# e-ink-display-v003.net
KiCad netlist of a schematic drawn in EAGLE
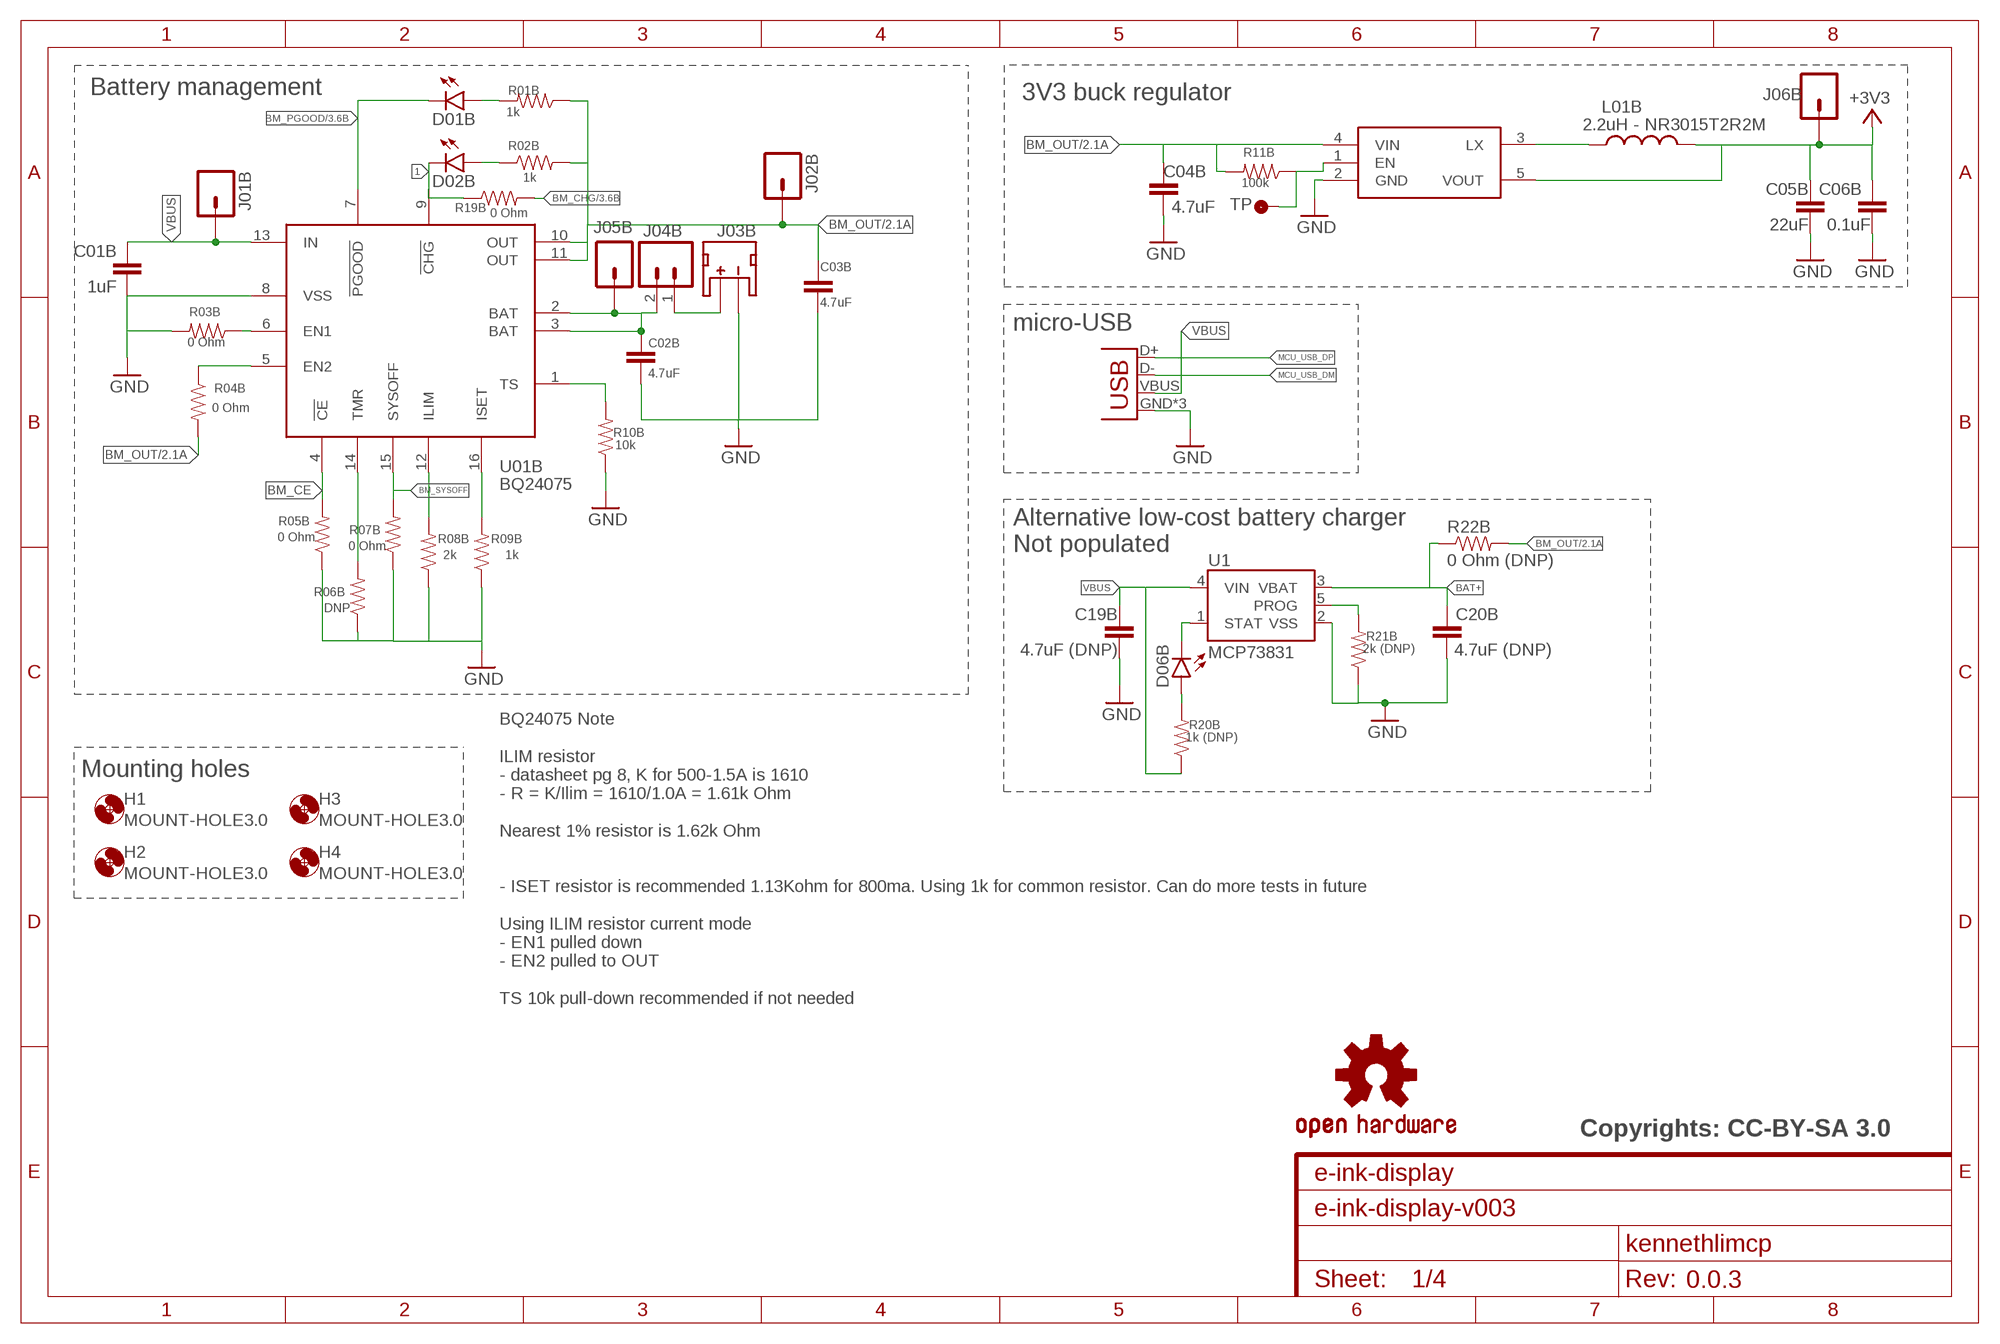
[diagram p0: schematic, sheet 1]
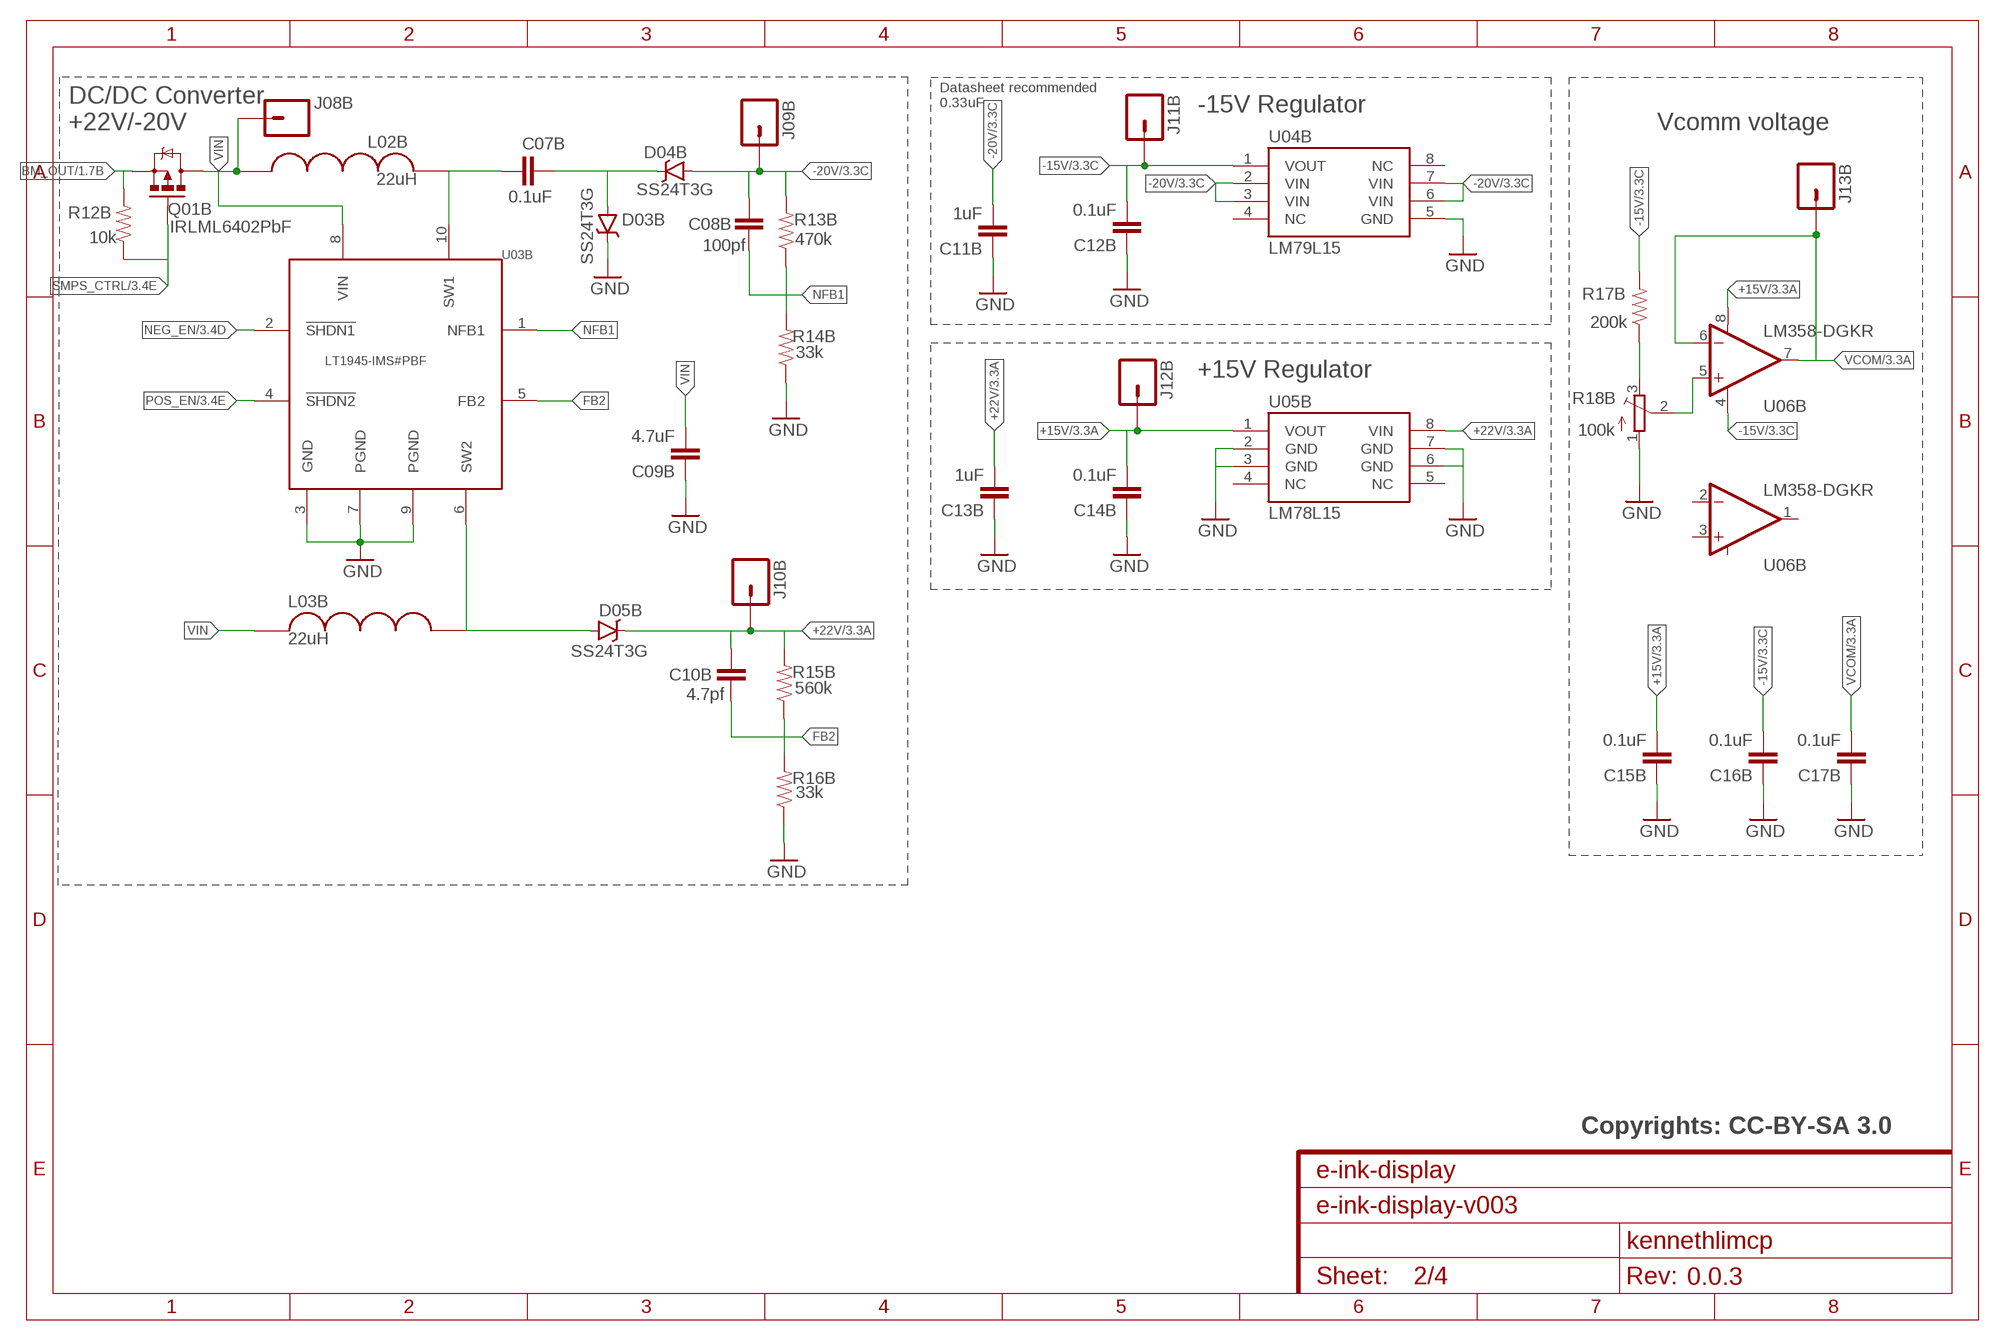
[diagram p1: schematic, sheet 2]
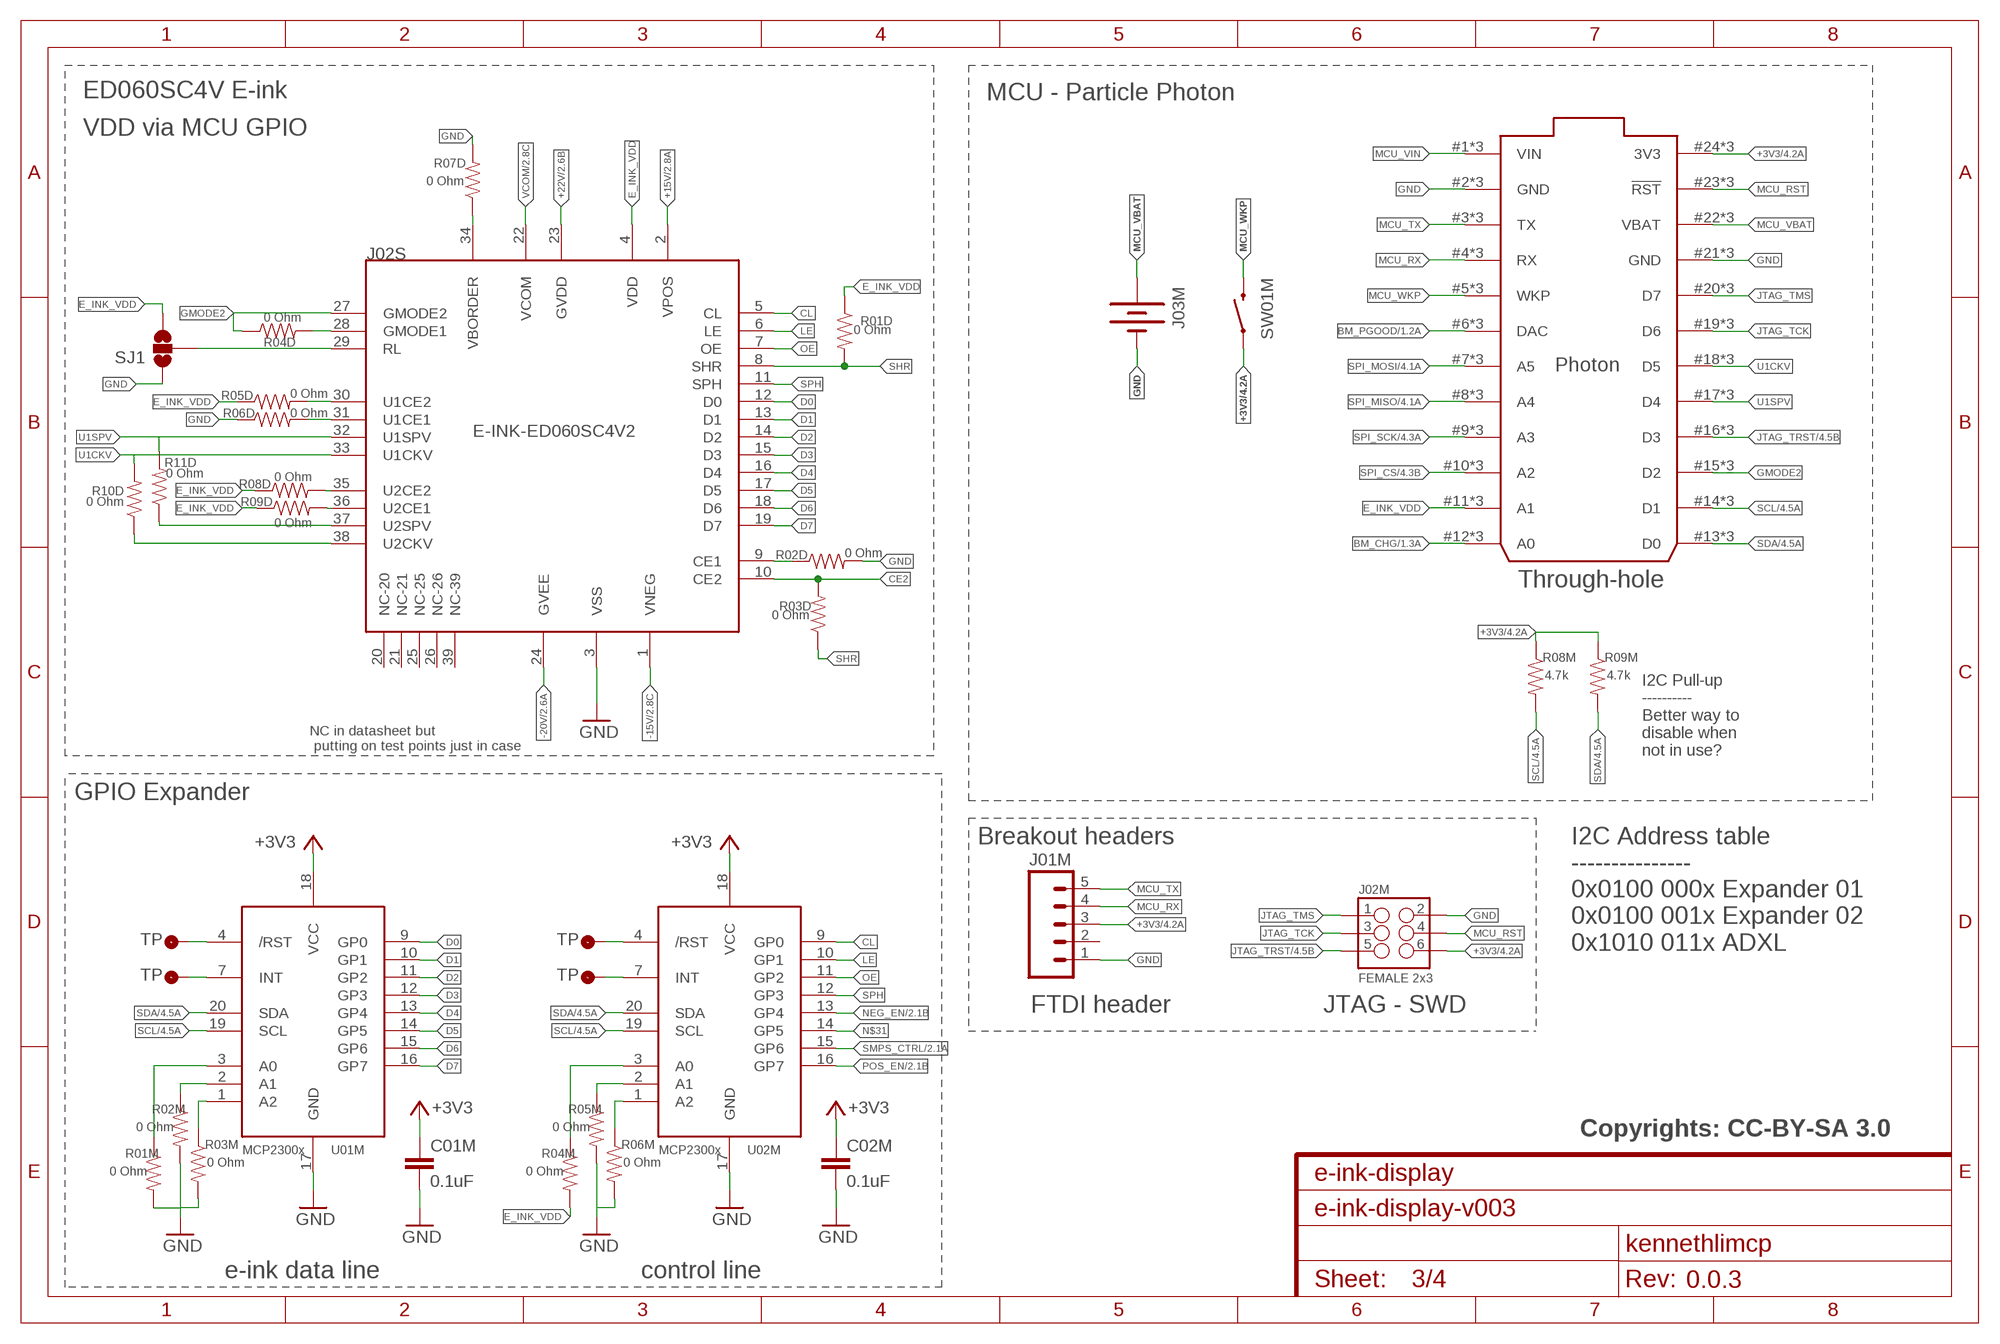
[diagram p2: schematic, sheet 3]
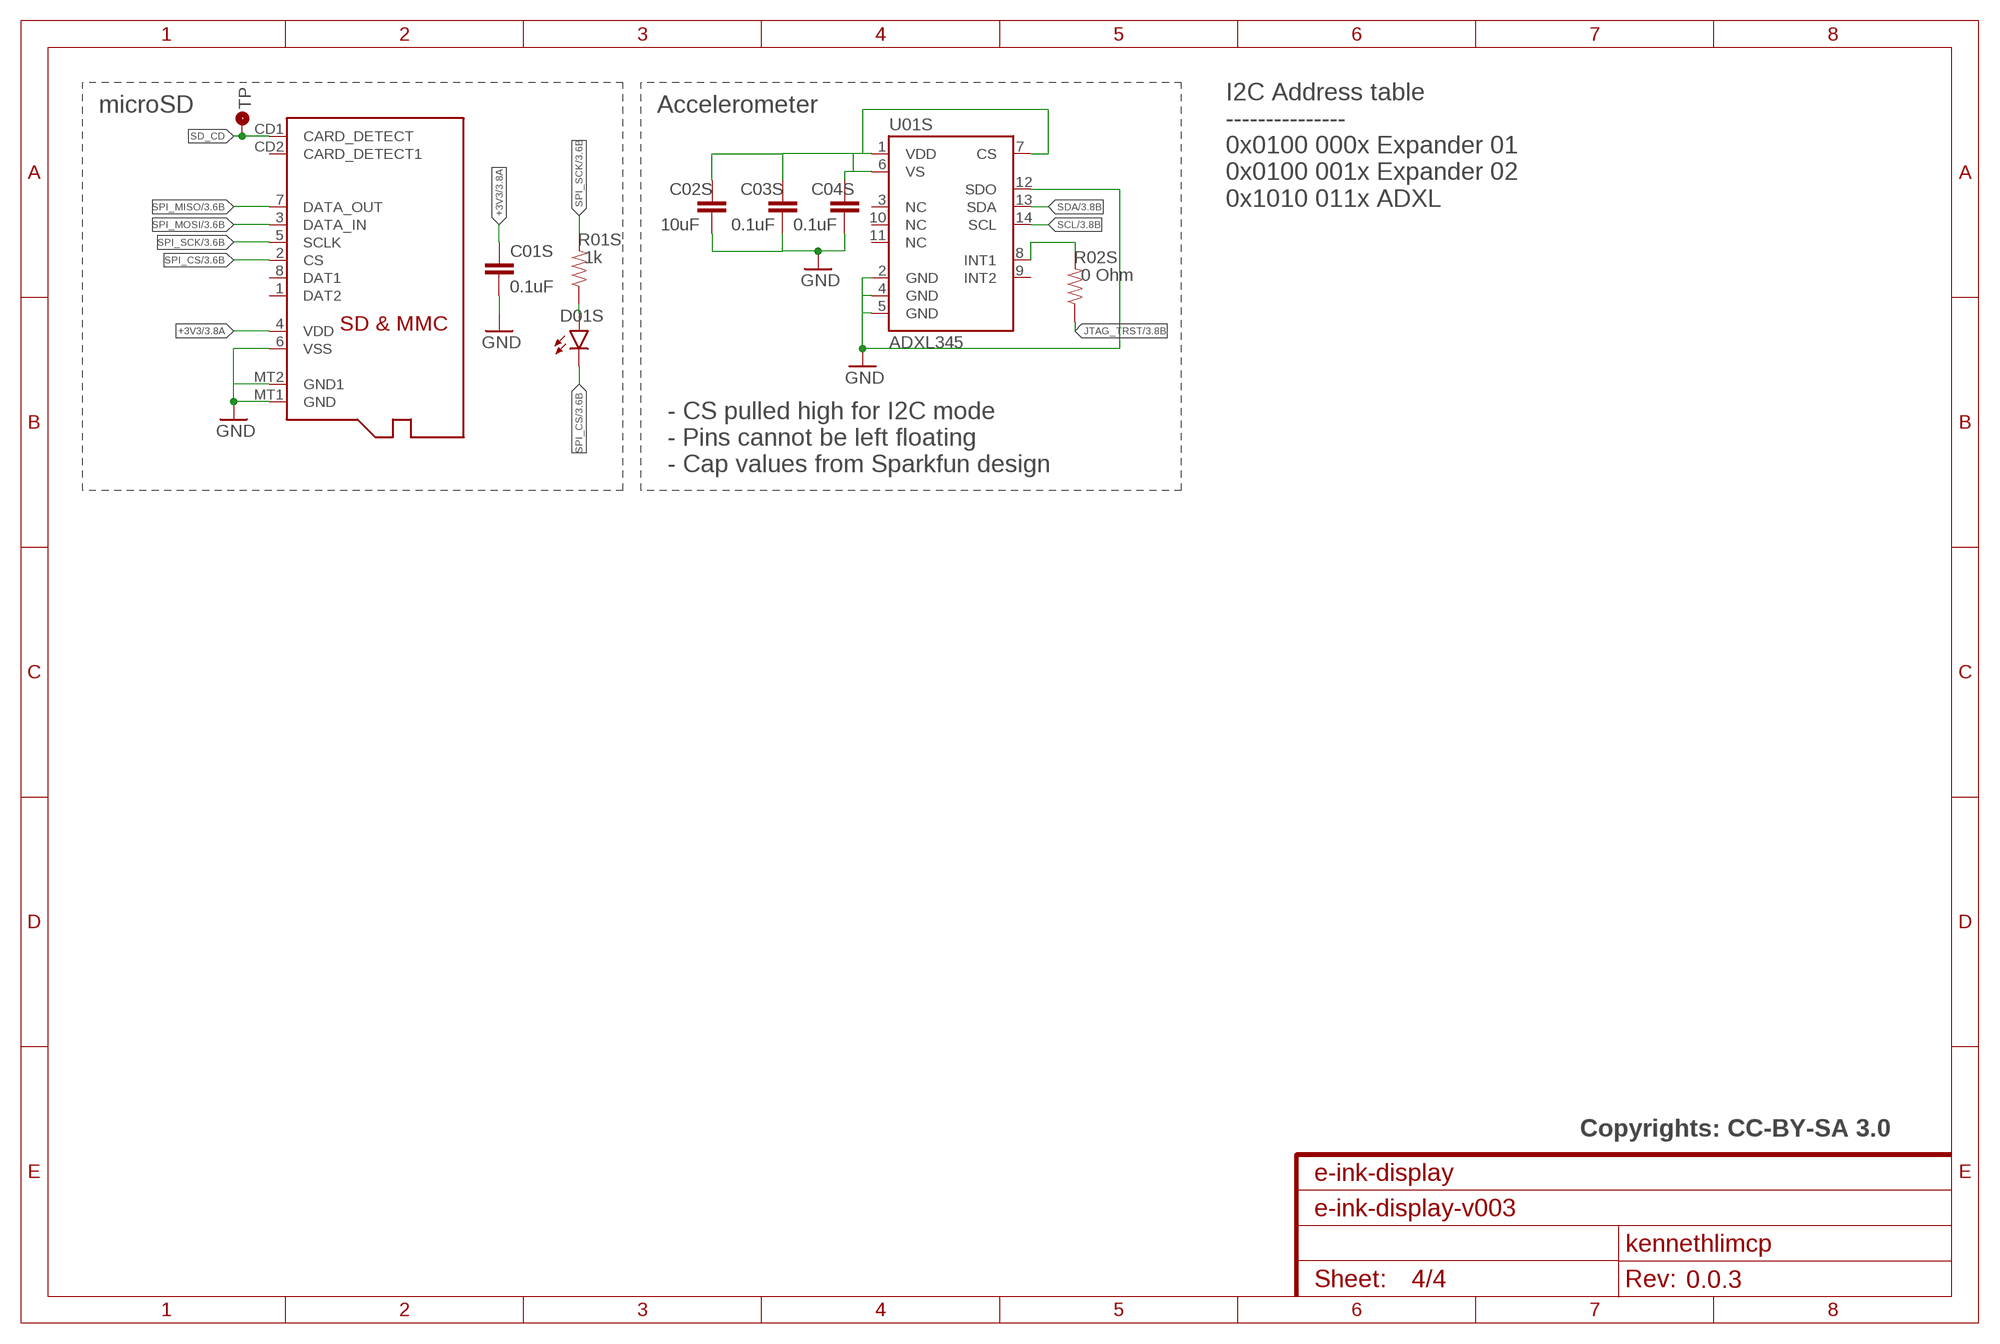
[diagram p3: schematic, sheet 4]

(export (version "E")
  (design (tool "Eeschema 10.0.6"))
  (components
    (comp (ref "C07B")
      (value "0.1uF")
      (footprint "eagle-import:0603-CAP")
      (libsource (lib "eagle-import") (part "CAP0603-CAP"))
    )
    (comp (ref "C08B")
      (value "100pf")
      (footprint "eagle-import:0603-CAP")
      (libsource (lib "eagle-import") (part "CAP0603-CAP"))
    )
    (comp (ref "C09B")
      (value "4.7uF")
      (footprint "eagle-import:0603-CAP")
      (libsource (lib "eagle-import") (part "CAP0603-CAP"))
    )
    (comp (ref "C10B")
      (value "4.7pf")
      (footprint "eagle-import:0603-CAP")
      (libsource (lib "eagle-import") (part "CAP0603-CAP"))
    )
    (comp (ref "C11B")
      (value "1uF")
      (footprint "eagle-import:0603-CAP")
      (libsource (lib "eagle-import") (part "CAP0603-CAP"))
    )
    (comp (ref "C12B")
      (value "0.1uF")
      (footprint "eagle-import:0603-CAP")
      (libsource (lib "eagle-import") (part "CAP0603-CAP"))
    )
    (comp (ref "C13B")
      (value "1uF")
      (footprint "eagle-import:0603-CAP")
      (libsource (lib "eagle-import") (part "CAP0603-CAP"))
    )
    (comp (ref "C14B")
      (value "0.1uF")
      (footprint "eagle-import:0603-CAP")
      (libsource (lib "eagle-import") (part "CAP0603-CAP"))
    )
    (comp (ref "C15B")
      (value "0.1uF")
      (footprint "eagle-import:0603-CAP")
      (libsource (lib "eagle-import") (part "CAP0603-CAP"))
    )
    (comp (ref "C16B")
      (value "0.1uF")
      (footprint "eagle-import:0603-CAP")
      (libsource (lib "eagle-import") (part "CAP0603-CAP"))
    )
    (comp (ref "C17B")
      (value "0.1uF")
      (footprint "eagle-import:0603-CAP")
      (libsource (lib "eagle-import") (part "CAP0603-CAP"))
    )
    (comp (ref "D03B")
      (value "SS24T3G")
      (footprint "eagle-import:SMA-DIODE")
      (libsource (lib "eagle-import") (part "SS24T3G"))
    )
    (comp (ref "D04B")
      (value "SS24T3G")
      (footprint "eagle-import:SMA-DIODE")
      (libsource (lib "eagle-import") (part "SS24T3G"))
    )
    (comp (ref "D05B")
      (value "SS24T3G")
      (footprint "eagle-import:SMA-DIODE")
      (libsource (lib "eagle-import") (part "SS24T3G"))
    )
    (comp (ref "J08B")
      (value "M01PTH")
      (footprint "eagle-import:1X01")
      (libsource (lib "eagle-import") (part "M01PTH"))
    )
    (comp (ref "J09B")
      (value "M01PTH")
      (footprint "eagle-import:1X01")
      (libsource (lib "eagle-import") (part "M01PTH"))
    )
    (comp (ref "J10B")
      (value "M01PTH")
      (footprint "eagle-import:1X01")
      (libsource (lib "eagle-import") (part "M01PTH"))
    )
    (comp (ref "J11B")
      (value "M01PTH")
      (footprint "eagle-import:1X01")
      (libsource (lib "eagle-import") (part "M01PTH"))
    )
    (comp (ref "J12B")
      (value "M01PTH")
      (footprint "eagle-import:1X01")
      (libsource (lib "eagle-import") (part "M01PTH"))
    )
    (comp (ref "J13B")
      (value "M01PTH")
      (footprint "eagle-import:1X01")
      (libsource (lib "eagle-import") (part "M01PTH"))
    )
    (comp (ref "L02B")
      (value "22uH")
      (footprint "eagle-import:4040(1515)")
      (libsource (lib "eagle-import") (part "INDUCTOR"))
    )
    (comp (ref "L03B")
      (value "22uH")
      (footprint "eagle-import:4040(1515)")
      (libsource (lib "eagle-import") (part "INDUCTOR"))
    )
    (comp (ref "Q01B")
      (value "IRLML6402PbF")
      (footprint "eagle-import:SOT23-3")
      (libsource (lib "eagle-import") (part "MOSFET-PCHANNELSMD"))
    )
    (comp (ref "R12B")
      (value "10k")
      (footprint "eagle-import:0603-RES")
      (libsource (lib "eagle-import") (part "RESISTOR0603"))
    )
    (comp (ref "R13B")
      (value "470k")
      (footprint "eagle-import:0603-RES")
      (libsource (lib "eagle-import") (part "RESISTOR0603"))
    )
    (comp (ref "R14B")
      (value "33k")
      (footprint "eagle-import:0603-RES")
      (libsource (lib "eagle-import") (part "RESISTOR0603"))
    )
    (comp (ref "R15B")
      (value "560k")
      (footprint "eagle-import:0603-RES")
      (libsource (lib "eagle-import") (part "RESISTOR0603"))
    )
    (comp (ref "R16B")
      (value "33k")
      (footprint "eagle-import:0603-RES")
      (libsource (lib "eagle-import") (part "RESISTOR0603"))
    )
    (comp (ref "R17B")
      (value "200k")
      (footprint "eagle-import:0603-RES")
      (libsource (lib "eagle-import") (part "RESISTOR0603"))
    )
    (comp (ref "R18B")
      (value "100k")
      (footprint "eagle-import:TC33X")
      (libsource (lib "eagle-import") (part "TRIMPOTTC33X"))
    )
    (comp (ref "U03B")
      (value "LT1945-IMS#PBF")
      (footprint "eagle-import:MSOP-10")
      (libsource (lib "eagle-import") (part "LT1945-IMS#PBF"))
    )
    (comp (ref "U04B")
      (value "LM79L15")
      (footprint "eagle-import:SO08")
      (libsource (lib "eagle-import") (part "LM79L15"))
    )
    (comp (ref "U05B")
      (value "LM78L15")
      (footprint "eagle-import:SO08")
      (libsource (lib "eagle-import") (part "LM78L15"))
    )
    (comp (ref "U06B")
      (value "LM358-DGKR")
      (footprint "eagle-import:MSOP-8")
      (libsource (lib "eagle-import") (part "LM358-DGKR"))
    )
    (comp (ref "C01S")
      (value "0.1uF")
      (footprint "eagle-import:0603-CAP")
      (libsource (lib "eagle-import") (part "CAP0603-CAP"))
    )
    (comp (ref "C02S")
      (value "10uF")
      (footprint "eagle-import:0603-CAP")
      (libsource (lib "eagle-import") (part "CAP0603-CAP"))
    )
    (comp (ref "C03S")
      (value "0.1uF")
      (footprint "eagle-import:0603-CAP")
      (libsource (lib "eagle-import") (part "CAP0603-CAP"))
    )
    (comp (ref "C04S")
      (value "0.1uF")
      (footprint "eagle-import:0603-CAP")
      (libsource (lib "eagle-import") (part "CAP0603-CAP"))
    )
    (comp (ref "D01S")
      (value "LED0603")
      (footprint "eagle-import:LED-0603")
      (libsource (lib "eagle-import") (part "LED0603"))
    )
    (comp (ref "J01S")
      (value "MICROSD")
      (footprint "eagle-import:MICROSD")
      (libsource (lib "eagle-import") (part "MICROSD"))
    )
    (comp (ref "R01S")
      (value "1k")
      (footprint "eagle-import:0603-RES")
      (libsource (lib "eagle-import") (part "SparkFun-Resistors_RESISTOR0603-RES"))
    )
    (comp (ref "R02S")
      (value "0 Ohm")
      (footprint "eagle-import:0603-RES")
      (libsource (lib "eagle-import") (part "RESISTOR0603"))
    )
    (comp (ref "U$5")
      (value "TP3")
      (footprint "eagle-import:TP60_BOT")
      (libsource (lib "eagle-import") (part "TP3"))
    )
    (comp (ref "U01S")
      (value "ADXL345")
      (footprint "eagle-import:LGA14")
      (libsource (lib "eagle-import") (part "ADXL345"))
    )
    (comp (ref "C01M")
      (value "0.1uF")
      (footprint "eagle-import:0603-CAP")
      (libsource (lib "eagle-import") (part "CAP0603-CAP"))
    )
    (comp (ref "C02M")
      (value "0.1uF")
      (footprint "eagle-import:0603-CAP")
      (libsource (lib "eagle-import") (part "CAP0603-CAP"))
    )
    (comp (ref "J01M")
      (value "M05PTH")
      (footprint "eagle-import:1X05")
      (libsource (lib "eagle-import") (part "M05PTH"))
    )
    (comp (ref "J02M")
      (value "FEMALE 2x3")
      (footprint "eagle-import:2X3")
      (libsource (lib "eagle-import") (part "M03X2FEMALE"))
    )
    (comp (ref "J02S")
      (value "E-INK-ED060SC4V2")
      (footprint "eagle-import:FPC-0.3-39")
      (libsource (lib "eagle-import") (part "E-INK-ED060SC4V2"))
    )
    (comp (ref "J03M")
      (value "BATTERY20PTH")
      (footprint "eagle-import:BATTCOM_20MM_PTH")
      (libsource (lib "eagle-import") (part "BATTERY20PTH"))
    )
    (comp (ref "R01D")
      (value "0 Ohm")
      (footprint "eagle-import:0603-RES")
      (libsource (lib "eagle-import") (part "RESISTOR0603-RES"))
    )
    (comp (ref "R01M")
      (value "0 Ohm")
      (footprint "eagle-import:0603-RES")
      (libsource (lib "eagle-import") (part "RESISTOR0603-RES"))
    )
    (comp (ref "R02D")
      (value "0 Ohm")
      (footprint "eagle-import:0603-RES")
      (libsource (lib "eagle-import") (part "RESISTOR0603-RES"))
    )
    (comp (ref "R02M")
      (value "0 Ohm")
      (footprint "eagle-import:0603-RES")
      (libsource (lib "eagle-import") (part "RESISTOR0603-RES"))
    )
    (comp (ref "R03D")
      (value "0 Ohm")
      (footprint "eagle-import:0603-RES")
      (libsource (lib "eagle-import") (part "RESISTOR0603-RES"))
    )
    (comp (ref "R03M")
      (value "0 Ohm")
      (footprint "eagle-import:0603-RES")
      (libsource (lib "eagle-import") (part "RESISTOR0603-RES"))
    )
    (comp (ref "R04D")
      (value "0 Ohm")
      (footprint "eagle-import:0603-RES")
      (libsource (lib "eagle-import") (part "RESISTOR0603-RES"))
    )
    (comp (ref "R04M")
      (value "0 Ohm")
      (footprint "eagle-import:0603-RES")
      (libsource (lib "eagle-import") (part "RESISTOR0603-RES"))
    )
    (comp (ref "R05D")
      (value "0 Ohm")
      (footprint "eagle-import:0603-RES")
      (libsource (lib "eagle-import") (part "RESISTOR0603-RES"))
    )
    (comp (ref "R05M")
      (value "0 Ohm")
      (footprint "eagle-import:0603-RES")
      (libsource (lib "eagle-import") (part "RESISTOR0603-RES"))
    )
    (comp (ref "R06D")
      (value "0 Ohm")
      (footprint "eagle-import:0603-RES")
      (libsource (lib "eagle-import") (part "RESISTOR0603-RES"))
    )
    (comp (ref "R06M")
      (value "0 Ohm")
      (footprint "eagle-import:0603-RES")
      (libsource (lib "eagle-import") (part "RESISTOR0603-RES"))
    )
    (comp (ref "R07D")
      (value "0 Ohm")
      (footprint "eagle-import:0603-RES")
      (libsource (lib "eagle-import") (part "RESISTOR0603-RES"))
    )
    (comp (ref "R08D")
      (value "0 Ohm")
      (footprint "eagle-import:0603-RES")
      (libsource (lib "eagle-import") (part "RESISTOR0603-RES"))
    )
    (comp (ref "R08M")
      (value "4.7k")
      (footprint "eagle-import:0603-RES")
      (libsource (lib "eagle-import") (part "RESISTOR0603-RES"))
    )
    (comp (ref "R09D")
      (value "0 Ohm")
      (footprint "eagle-import:0603-RES")
      (libsource (lib "eagle-import") (part "RESISTOR0603-RES"))
    )
    (comp (ref "R09M")
      (value "4.7k")
      (footprint "eagle-import:0603-RES")
      (libsource (lib "eagle-import") (part "RESISTOR0603-RES"))
    )
    (comp (ref "R10D")
      (value "0 Ohm")
      (footprint "eagle-import:0603-RES")
      (libsource (lib "eagle-import") (part "RESISTOR0603-RES"))
    )
    (comp (ref "R11D")
      (value "0 Ohm")
      (footprint "eagle-import:0603-RES")
      (libsource (lib "eagle-import") (part "RESISTOR0603-RES"))
    )
    (comp (ref "SJ1")
      (value "SOLDERJUMPER_2WAYT")
      (footprint "eagle-import:SJ_2")
      (libsource (lib "eagle-import") (part "SOLDERJUMPER_2WAYT"))
    )
    (comp (ref "SW01M")
      (value "SWITCH-MOMENTARY-2PTH")
      (footprint "eagle-import:TACTILE-PTH")
      (libsource (lib "eagle-import") (part "SWITCH-MOMENTARY-2PTH"))
    )
    (comp (ref "U$1")
      (value "TP1")
      (footprint "eagle-import:TP35_BOT")
      (libsource (lib "eagle-import") (part "TP1"))
    )
    (comp (ref "U$2")
      (value "TP1")
      (footprint "eagle-import:TP35_BOT")
      (libsource (lib "eagle-import") (part "TP1"))
    )
    (comp (ref "U$3")
      (value "TP1")
      (footprint "eagle-import:TP35_BOT")
      (libsource (lib "eagle-import") (part "TP1"))
    )
    (comp (ref "U$4")
      (value "TP1")
      (footprint "eagle-import:TP35_BOT")
      (libsource (lib "eagle-import") (part "TP1"))
    )
    (comp (ref "U01M")
      (value "MCP2300X/QFN")
      (footprint "eagle-import:QFN-20(4X4)")
      (libsource (lib "eagle-import") (part "MCP2300X/QFN"))
    )
    (comp (ref "U02M")
      (value "MCP2300X/QFN")
      (footprint "eagle-import:QFN-20(4X4)")
      (libsource (lib "eagle-import") (part "MCP2300X/QFN"))
    )
    (comp (ref "U03M")
      (value "PHOTON_WITH_STACKABLE_HEADERS")
      (footprint "eagle-import:PHOTON_STACKABLE")
      (libsource (lib "eagle-import") (part "PHOTON_WITH_STACKABLE_HEADERS"))
    )
    (comp (ref "C01B")
      (value "1uF")
      (footprint "eagle-import:0603-CAP")
      (libsource (lib "eagle-import") (part "CAP0603-CAP"))
    )
    (comp (ref "C02B")
      (value "4.7uF")
      (footprint "eagle-import:0603-CAP")
      (libsource (lib "eagle-import") (part "CAP0603-CAP"))
    )
    (comp (ref "C03B")
      (value "4.7uF")
      (footprint "eagle-import:0603-CAP")
      (libsource (lib "eagle-import") (part "CAP0603-CAP"))
    )
    (comp (ref "C04B")
      (value "4.7uF")
      (footprint "eagle-import:0603-CAP")
      (libsource (lib "eagle-import") (part "CAP0603-CAP"))
    )
    (comp (ref "C05B")
      (value "22uF")
      (footprint "eagle-import:0603-CAP")
      (libsource (lib "eagle-import") (part "CAP0603-CAP"))
    )
    (comp (ref "C06B")
      (value "0.1uF")
      (footprint "eagle-import:0603-CAP")
      (libsource (lib "eagle-import") (part "CAP0603-CAP"))
    )
    (comp (ref "C19B")
      (value "4.7uF (DNP)")
      (footprint "eagle-import:0603-CAP")
      (libsource (lib "eagle-import") (part "CAP0603-CAP"))
    )
    (comp (ref "C20B")
      (value "4.7uF (DNP)")
      (footprint "eagle-import:0603-CAP")
      (libsource (lib "eagle-import") (part "CAP0603-CAP"))
    )
    (comp (ref "D01B")
      (value "LED0603")
      (footprint "eagle-import:LED-0603")
      (libsource (lib "eagle-import") (part "LED0603"))
    )
    (comp (ref "D02B")
      (value "LED0603")
      (footprint "eagle-import:LED-0603")
      (libsource (lib "eagle-import") (part "LED0603"))
    )
    (comp (ref "D06B")
      (value "LED0603")
      (footprint "eagle-import:LED-0603")
      (libsource (lib "eagle-import") (part "LED0603"))
    )
    (comp (ref "H1")
      (value "MOUNT-HOLE3.0")
      (footprint "eagle-import:3,0")
      (libsource (lib "eagle-import") (part "MOUNT-HOLE3.0"))
    )
    (comp (ref "H2")
      (value "MOUNT-HOLE3.0")
      (footprint "eagle-import:3,0")
      (libsource (lib "eagle-import") (part "MOUNT-HOLE3.0"))
    )
    (comp (ref "H3")
      (value "MOUNT-HOLE3.0")
      (footprint "eagle-import:3,0")
      (libsource (lib "eagle-import") (part "MOUNT-HOLE3.0"))
    )
    (comp (ref "H4")
      (value "MOUNT-HOLE3.0")
      (footprint "eagle-import:3,0")
      (libsource (lib "eagle-import") (part "MOUNT-HOLE3.0"))
    )
    (comp (ref "J01B")
      (value "M01PTH")
      (footprint "eagle-import:1X01")
      (libsource (lib "eagle-import") (part "M01PTH"))
    )
    (comp (ref "J02B")
      (value "M01PTH")
      (footprint "eagle-import:1X01")
      (libsource (lib "eagle-import") (part "M01PTH"))
    )
    (comp (ref "J03B")
      (value "JST_2MM_MALE")
      (footprint "eagle-import:JST-2-SMD")
      (libsource (lib "eagle-import") (part "JST_2MM_MALE"))
    )
    (comp (ref "J04B")
      (value "M02PTH")
      (footprint "eagle-import:1X02")
      (libsource (lib "eagle-import") (part "M02PTH"))
    )
    (comp (ref "J05B")
      (value "M01PTH")
      (footprint "eagle-import:1X01")
      (libsource (lib "eagle-import") (part "M01PTH"))
    )
    (comp (ref "J06B")
      (value "M01PTH")
      (footprint "eagle-import:1X01")
      (libsource (lib "eagle-import") (part "M01PTH"))
    )
    (comp (ref "J07B")
      (value "USBUSB-MICROB-SLOT-HOLE")
      (footprint "eagle-import:USB-MICROB-SLOT-HOLE")
      (libsource (lib "eagle-import") (part "USBUSB-MICROB-SLOT-HOLE"))
    )
    (comp (ref "L01B")
      (value "2.2uH - NR3015T2R2M")
      (footprint "eagle-import:INDUCTOR-NR3015")
      (libsource (lib "eagle-import") (part "INDUCTOR-SPARKFUNNR3015T4R7M"))
    )
    (comp (ref "LOGO1")
      (value "OSHW-LOGOPAD")
      (footprint "eagle-import:OSHW-LOGO-M-PAD")
      (libsource (lib "eagle-import") (part "OSHW-LOGOPAD"))
    )
    (comp (ref "R01B")
      (value "1k")
      (footprint "eagle-import:0603-RES")
      (libsource (lib "eagle-import") (part "SparkFun-Resistors_RESISTOR0603-RES"))
    )
    (comp (ref "R02B")
      (value "1k")
      (footprint "eagle-import:0603-RES")
      (libsource (lib "eagle-import") (part "SparkFun-Resistors_RESISTOR0603-RES"))
    )
    (comp (ref "R03B")
      (value "0 Ohm")
      (footprint "eagle-import:0603-RES")
      (libsource (lib "eagle-import") (part "SparkFun-Resistors_RESISTOR0603-RES"))
    )
    (comp (ref "R04B")
      (value "0 Ohm")
      (footprint "eagle-import:0603-RES")
      (libsource (lib "eagle-import") (part "RESISTOR0603"))
    )
    (comp (ref "R05B")
      (value "0 Ohm")
      (footprint "eagle-import:0603-RES")
      (libsource (lib "eagle-import") (part "RESISTOR0603"))
    )
    (comp (ref "R06B")
      (value "DNP")
      (footprint "eagle-import:0603-RES")
      (libsource (lib "eagle-import") (part "RESISTOR0603"))
    )
    (comp (ref "R07B")
      (value "0 Ohm")
      (footprint "eagle-import:0603-RES")
      (libsource (lib "eagle-import") (part "RESISTOR0603"))
    )
    (comp (ref "R08B")
      (value "2k")
      (footprint "eagle-import:0603-RES")
      (libsource (lib "eagle-import") (part "RESISTOR0603"))
    )
    (comp (ref "R09B")
      (value "1k")
      (footprint "eagle-import:0603-RES")
      (libsource (lib "eagle-import") (part "SparkFun-Resistors_RESISTOR0603-RES"))
    )
    (comp (ref "R10B")
      (value "10k")
      (footprint "eagle-import:0603-RES")
      (libsource (lib "eagle-import") (part "RESISTOR0603"))
    )
    (comp (ref "R11B")
      (value "100k")
      (footprint "eagle-import:0603-RES")
      (libsource (lib "eagle-import") (part "RESISTOR0603"))
    )
    (comp (ref "R19B")
      (value "0 Ohm")
      (footprint "eagle-import:0603-RES")
      (libsource (lib "eagle-import") (part "RESISTOR0603"))
    )
    (comp (ref "R20B")
      (value "1k (DNP)")
      (footprint "eagle-import:0603-RES")
      (libsource (lib "eagle-import") (part "RESISTOR0603"))
    )
    (comp (ref "R21B")
      (value "2k (DNP)")
      (footprint "eagle-import:0603-RES")
      (libsource (lib "eagle-import") (part "RESISTOR0603"))
    )
    (comp (ref "R22B")
      (value "0 Ohm (DNP)")
      (footprint "eagle-import:1206")
      (libsource (lib "eagle-import") (part "SparkFun-Resistors_RESISTOR1206"))
    )
    (comp (ref "TP01B")
      (value "TP1")
      (footprint "eagle-import:TP35_BOT")
      (libsource (lib "eagle-import") (part "TP1"))
    )
    (comp (ref "U1")
      (value "MCP73831")
      (footprint "eagle-import:SOT23-5")
      (libsource (lib "eagle-import") (part "MCP73831"))
    )
    (comp (ref "U01B")
      (value "BQ24075")
      (footprint "eagle-import:QFN-16")
      (libsource (lib "eagle-import") (part "BQ24075"))
    )
    (comp (ref "U02B")
      (value "R8008-33")
      (footprint "eagle-import:SOT23-5")
      (libsource (lib "eagle-import") (part "R8008-33"))
    )
  )
  (nets
    (net (code "1") (name "+3V3") (class "Default")
      (node (ref "C01M") (pin "1") (pinfunction "1_1") (pintype "passive"))
      (node (ref "C01S") (pin "1") (pinfunction "1_1") (pintype "passive"))
      (node (ref "C02M") (pin "1") (pinfunction "1_1") (pintype "passive"))
      (node (ref "C05B") (pin "2") (pinfunction "2_2") (pintype "passive"))
      (node (ref "C06B") (pin "2") (pinfunction "2_2") (pintype "passive"))
      (node (ref "J01M") (pin "3") (pinfunction "3_3") (pintype "passive"))
      (node (ref "J01S") (pin "4") (pinfunction "VDD_4") (pintype "power_in"))
      (node (ref "J02M") (pin "6") (pinfunction "6_6") (pintype "bidirectional"))
      (node (ref "J06B") (pin "1") (pinfunction "1_1") (pintype "passive"))
      (node (ref "L01B") (pin "2") (pinfunction "2_2") (pintype "passive"))
      (node (ref "R08M") (pin "1") (pinfunction "1_1") (pintype "passive"))
      (node (ref "R09M") (pin "1") (pinfunction "1_1") (pintype "passive"))
      (node (ref "SW01M") (pin "1") (pinfunction "1_1") (pintype "passive"))
      (node (ref "U01M") (pin "18") (pinfunction "VCC_18") (pintype "power_in"))
      (node (ref "U02B") (pin "5") (pinfunction "VOUT_5") (pintype "bidirectional"))
      (node (ref "U02M") (pin "18") (pinfunction "VCC_18") (pintype "power_in"))
      (node (ref "U03M") (pin "#24") (pinfunction "3V3_#24") (pintype "power_in"))
      (node (ref "U03M") (pin "24") (pinfunction "3V3_24") (pintype "power_in"))
      (node (ref "U03M") (pin "@24") (pinfunction "3V3_@24") (pintype "power_in"))
    )
    (net (code "2") (name "+15V") (class "Default")
      (node (ref "C14B") (pin "2") (pinfunction "2_2") (pintype "passive"))
      (node (ref "C15B") (pin "2") (pinfunction "2_2") (pintype "passive"))
      (node (ref "J02S") (pin "2") (pinfunction "VPOS_2") (pintype "bidirectional"))
      (node (ref "J12B") (pin "1") (pinfunction "1_1") (pintype "passive"))
      (node (ref "U05B") (pin "1") (pinfunction "VOUT_1") (pintype "bidirectional"))
      (node (ref "U06B") (pin "8") (pinfunction "V+_8") (pintype "power_in"))
    )
    (net (code "3") (name "+22V") (class "Default")
      (node (ref "C10B") (pin "2") (pinfunction "2_2") (pintype "passive"))
      (node (ref "C13B") (pin "2") (pinfunction "2_2") (pintype "passive"))
      (node (ref "D05B") (pin "C") (pinfunction "C_C") (pintype "passive"))
      (node (ref "J02S") (pin "23") (pinfunction "GVDD_23") (pintype "bidirectional"))
      (node (ref "J10B") (pin "1") (pinfunction "1_1") (pintype "passive"))
      (node (ref "R15B") (pin "2") (pinfunction "2_2") (pintype "passive"))
      (node (ref "U05B") (pin "8") (pinfunction "VIN_8") (pintype "bidirectional"))
    )
    (net (code "4") (name "-15V") (class "Default")
      (node (ref "C12B") (pin "2") (pinfunction "2_2") (pintype "passive"))
      (node (ref "C16B") (pin "2") (pinfunction "2_2") (pintype "passive"))
      (node (ref "J02S") (pin "1") (pinfunction "VNEG_1") (pintype "bidirectional"))
      (node (ref "J11B") (pin "1") (pinfunction "1_1") (pintype "passive"))
      (node (ref "R17B") (pin "2") (pinfunction "2_2") (pintype "passive"))
      (node (ref "U04B") (pin "1") (pinfunction "VOUT_1") (pintype "bidirectional"))
      (node (ref "U06B") (pin "4") (pinfunction "V-_4") (pintype "power_in"))
    )
    (net (code "5") (name "-20V") (class "Default")
      (node (ref "C08B") (pin "2") (pinfunction "2_2") (pintype "passive"))
      (node (ref "C11B") (pin "2") (pinfunction "2_2") (pintype "passive"))
      (node (ref "D04B") (pin "A") (pinfunction "A_A") (pintype "passive"))
      (node (ref "J02S") (pin "24") (pinfunction "GVEE_24") (pintype "bidirectional"))
      (node (ref "J09B") (pin "1") (pinfunction "1_1") (pintype "passive"))
      (node (ref "R13B") (pin "2") (pinfunction "2_2") (pintype "passive"))
      (node (ref "U04B") (pin "2") (pinfunction "VIN_2") (pintype "bidirectional"))
      (node (ref "U04B") (pin "3") (pinfunction "VIN_3") (pintype "bidirectional"))
      (node (ref "U04B") (pin "6") (pinfunction "VIN_6") (pintype "bidirectional"))
      (node (ref "U04B") (pin "7") (pinfunction "VIN_7") (pintype "bidirectional"))
    )
    (net (code "6") (name "1") (class "Default")
      (node (ref "D02B") (pin "C") (pinfunction "C_C") (pintype "passive"))
      (node (ref "R19B") (pin "1") (pinfunction "1_1") (pintype "passive"))
      (node (ref "U01B") (pin "9") (pinfunction "~{CHG}_9") (pintype "bidirectional"))
    )
    (net (code "7") (name "BAT+") (class "Default")
      (node (ref "C20B") (pin "2") (pinfunction "2_2") (pintype "passive"))
      (node (ref "J03B") (pin "2") (pinfunction "+_2") (pintype "bidirectional"))
      (node (ref "J04B") (pin "1") (pinfunction "1_1") (pintype "passive"))
      (node (ref "R22B") (pin "1") (pinfunction "1_1") (pintype "passive"))
      (node (ref "U1") (pin "3") (pinfunction "VBAT_3") (pintype "power_in"))
    )
    (net (code "8") (name "BM_CE") (class "Default")
      (node (ref "R05B") (pin "2") (pinfunction "2_2") (pintype "passive"))
      (node (ref "U01B") (pin "4") (pinfunction "~{CE}_4") (pintype "bidirectional"))
    )
    (net (code "9") (name "BM_CHG") (class "Default")
      (node (ref "R19B") (pin "2") (pinfunction "2_2") (pintype "passive"))
      (node (ref "U03M") (pin "#12") (pinfunction "A0_#12") (pintype "bidirectional"))
      (node (ref "U03M") (pin "12") (pinfunction "A0_12") (pintype "bidirectional"))
      (node (ref "U03M") (pin "@12") (pinfunction "A0_@12") (pintype "bidirectional"))
    )
    (net (code "10") (name "BM_OUT") (class "Default")
      (node (ref "C03B") (pin "2") (pinfunction "2_2") (pintype "passive"))
      (node (ref "C04B") (pin "2") (pinfunction "2_2") (pintype "passive"))
      (node (ref "J02B") (pin "1") (pinfunction "1_1") (pintype "passive"))
      (node (ref "Q01B") (pin "2") (pinfunction "S_2") (pintype "passive"))
      (node (ref "R01B") (pin "1") (pinfunction "1_1") (pintype "passive"))
      (node (ref "R02B") (pin "2") (pinfunction "2_2") (pintype "passive"))
      (node (ref "R04B") (pin "2") (pinfunction "2_2") (pintype "passive"))
      (node (ref "R11B") (pin "2") (pinfunction "2_2") (pintype "passive"))
      (node (ref "R12B") (pin "2") (pinfunction "2_2") (pintype "passive"))
      (node (ref "R22B") (pin "2") (pinfunction "2_2") (pintype "passive"))
      (node (ref "U01B") (pin "10") (pinfunction "OUT_10") (pintype "bidirectional"))
      (node (ref "U01B") (pin "11") (pinfunction "OUT_11") (pintype "bidirectional"))
      (node (ref "U02B") (pin "4") (pinfunction "VIN_4") (pintype "bidirectional"))
    )
    (net (code "11") (name "BM_PGOOD") (class "Default")
      (node (ref "D01B") (pin "C") (pinfunction "C_C") (pintype "passive"))
      (node (ref "U01B") (pin "7") (pinfunction "~{PGOOD}_7") (pintype "bidirectional"))
      (node (ref "U03M") (pin "#6") (pinfunction "DAC_#6") (pintype "bidirectional"))
      (node (ref "U03M") (pin "6") (pinfunction "DAC_6") (pintype "bidirectional"))
      (node (ref "U03M") (pin "@6") (pinfunction "DAC_@6") (pintype "bidirectional"))
    )
    (net (code "12") (name "BM_SYSOFF") (class "Default")
      (node (ref "R07B") (pin "2") (pinfunction "2_2") (pintype "passive"))
      (node (ref "U01B") (pin "15") (pinfunction "SYSOFF_15") (pintype "bidirectional"))
    )
    (net (code "13") (name "CE2") (class "Default")
      (node (ref "J02S") (pin "10") (pinfunction "CE2_10") (pintype "bidirectional"))
      (node (ref "R03D") (pin "2") (pinfunction "2_2") (pintype "passive"))
    )
    (net (code "14") (name "CL") (class "Default")
      (node (ref "J02S") (pin "5") (pinfunction "CL_5") (pintype "bidirectional"))
      (node (ref "U02M") (pin "9") (pinfunction "GP0_9") (pintype "bidirectional"))
    )
    (net (code "15") (name "D0") (class "Default")
      (node (ref "J02S") (pin "12") (pinfunction "D0_12") (pintype "bidirectional"))
      (node (ref "U01M") (pin "9") (pinfunction "GP0_9") (pintype "bidirectional"))
    )
    (net (code "16") (name "D1") (class "Default")
      (node (ref "J02S") (pin "13") (pinfunction "D1_13") (pintype "bidirectional"))
      (node (ref "U01M") (pin "10") (pinfunction "GP1_10") (pintype "bidirectional"))
    )
    (net (code "17") (name "D2") (class "Default")
      (node (ref "J02S") (pin "14") (pinfunction "D2_14") (pintype "bidirectional"))
      (node (ref "U01M") (pin "11") (pinfunction "GP2_11") (pintype "bidirectional"))
    )
    (net (code "18") (name "D3") (class "Default")
      (node (ref "J02S") (pin "15") (pinfunction "D3_15") (pintype "bidirectional"))
      (node (ref "U01M") (pin "12") (pinfunction "GP3_12") (pintype "bidirectional"))
    )
    (net (code "19") (name "D4") (class "Default")
      (node (ref "J02S") (pin "16") (pinfunction "D4_16") (pintype "bidirectional"))
      (node (ref "U01M") (pin "13") (pinfunction "GP4_13") (pintype "bidirectional"))
    )
    (net (code "20") (name "D5") (class "Default")
      (node (ref "J02S") (pin "17") (pinfunction "D5_17") (pintype "bidirectional"))
      (node (ref "U01M") (pin "14") (pinfunction "GP5_14") (pintype "bidirectional"))
    )
    (net (code "21") (name "D6") (class "Default")
      (node (ref "J02S") (pin "18") (pinfunction "D6_18") (pintype "bidirectional"))
      (node (ref "U01M") (pin "15") (pinfunction "GP6_15") (pintype "bidirectional"))
    )
    (net (code "22") (name "D7") (class "Default")
      (node (ref "J02S") (pin "19") (pinfunction "D7_19") (pintype "bidirectional"))
      (node (ref "U01M") (pin "16") (pinfunction "GP7_16") (pintype "bidirectional"))
    )
    (net (code "23") (name "E_INK_VDD") (class "Default")
      (node (ref "J02S") (pin "4") (pinfunction "VDD_4") (pintype "bidirectional"))
      (node (ref "R01D") (pin "1") (pinfunction "1_1") (pintype "passive"))
      (node (ref "R04M") (pin "2") (pinfunction "2_2") (pintype "passive"))
      (node (ref "R05D") (pin "1") (pinfunction "1_1") (pintype "passive"))
      (node (ref "R08D") (pin "1") (pinfunction "1_1") (pintype "passive"))
      (node (ref "R09D") (pin "1") (pinfunction "1_1") (pintype "passive"))
      (node (ref "SJ1") (pin "3") (pinfunction "3_3") (pintype "passive"))
      (node (ref "U03M") (pin "#11") (pinfunction "A1_#11") (pintype "bidirectional"))
      (node (ref "U03M") (pin "11") (pinfunction "A1_11") (pintype "bidirectional"))
      (node (ref "U03M") (pin "@11") (pinfunction "A1_@11") (pintype "bidirectional"))
    )
    (net (code "24") (name "FB2") (class "Default")
      (node (ref "C10B") (pin "1") (pinfunction "1_1") (pintype "passive"))
      (node (ref "R15B") (pin "1") (pinfunction "1_1") (pintype "passive"))
      (node (ref "R16B") (pin "2") (pinfunction "2_2") (pintype "passive"))
      (node (ref "U03B") (pin "5") (pinfunction "FB2_5") (pintype "bidirectional"))
    )
    (net (code "25") (name "GMODE2") (class "Default")
      (node (ref "J02S") (pin "27") (pinfunction "GMODE2_27") (pintype "bidirectional"))
      (node (ref "R04D") (pin "1") (pinfunction "1_1") (pintype "passive"))
      (node (ref "U03M") (pin "#15") (pinfunction "D2_#15") (pintype "bidirectional"))
      (node (ref "U03M") (pin "15") (pinfunction "D2_15") (pintype "bidirectional"))
      (node (ref "U03M") (pin "@15") (pinfunction "D2_@15") (pintype "bidirectional"))
    )
    (net (code "26") (name "GND") (class "Default")
      (node (ref "C01B") (pin "1") (pinfunction "1_1") (pintype "passive"))
      (node (ref "C01M") (pin "2") (pinfunction "2_2") (pintype "passive"))
      (node (ref "C01S") (pin "2") (pinfunction "2_2") (pintype "passive"))
      (node (ref "C02B") (pin "1") (pinfunction "1_1") (pintype "passive"))
      (node (ref "C02M") (pin "2") (pinfunction "2_2") (pintype "passive"))
      (node (ref "C02S") (pin "2") (pinfunction "2_2") (pintype "passive"))
      (node (ref "C03B") (pin "1") (pinfunction "1_1") (pintype "passive"))
      (node (ref "C03S") (pin "2") (pinfunction "2_2") (pintype "passive"))
      (node (ref "C04B") (pin "1") (pinfunction "1_1") (pintype "passive"))
      (node (ref "C04S") (pin "2") (pinfunction "2_2") (pintype "passive"))
      (node (ref "C05B") (pin "1") (pinfunction "1_1") (pintype "passive"))
      (node (ref "C06B") (pin "1") (pinfunction "1_1") (pintype "passive"))
      (node (ref "C09B") (pin "1") (pinfunction "1_1") (pintype "passive"))
      (node (ref "C11B") (pin "1") (pinfunction "1_1") (pintype "passive"))
      (node (ref "C12B") (pin "1") (pinfunction "1_1") (pintype "passive"))
      (node (ref "C13B") (pin "1") (pinfunction "1_1") (pintype "passive"))
      (node (ref "C14B") (pin "1") (pinfunction "1_1") (pintype "passive"))
      (node (ref "C15B") (pin "1") (pinfunction "1_1") (pintype "passive"))
      (node (ref "C16B") (pin "1") (pinfunction "1_1") (pintype "passive"))
      (node (ref "C17B") (pin "1") (pinfunction "1_1") (pintype "passive"))
      (node (ref "C19B") (pin "1") (pinfunction "1_1") (pintype "passive"))
      (node (ref "C20B") (pin "1") (pinfunction "1_1") (pintype "passive"))
      (node (ref "D03B") (pin "C") (pinfunction "C_C") (pintype "passive"))
      (node (ref "J01M") (pin "1") (pinfunction "1_1") (pintype "passive"))
      (node (ref "J01S") (pin "6") (pinfunction "VSS_6") (pintype "power_in"))
      (node (ref "J01S") (pin "MT1") (pinfunction "GND_MT1") (pintype "power_in"))
      (node (ref "J01S") (pin "MT2") (pinfunction "GND1_MT2") (pintype "power_in"))
      (node (ref "J02M") (pin "2") (pinfunction "2_2") (pintype "bidirectional"))
      (node (ref "J02S") (pin "3") (pinfunction "VSS_3") (pintype "bidirectional"))
      (node (ref "J03B") (pin "1") (pinfunction "-_1") (pintype "bidirectional"))
      (node (ref "J03M") (pin "2") (pinfunction "-_2") (pintype "power_in"))
      (node (ref "J07B") (pin "GND") (pinfunction "GND_GND") (pintype "bidirectional"))
      (node (ref "J07B") (pin "MT1") (pinfunction "GND_MT1") (pintype "bidirectional"))
      (node (ref "J07B") (pin "MT2") (pinfunction "GND_MT2") (pintype "bidirectional"))
      (node (ref "R01M") (pin "2") (pinfunction "2_2") (pintype "passive"))
      (node (ref "R02D") (pin "2") (pinfunction "2_2") (pintype "passive"))
      (node (ref "R02M") (pin "2") (pinfunction "2_2") (pintype "passive"))
      (node (ref "R03B") (pin "2") (pinfunction "2_2") (pintype "passive"))
      (node (ref "R03M") (pin "2") (pinfunction "2_2") (pintype "passive"))
      (node (ref "R05B") (pin "1") (pinfunction "1_1") (pintype "passive"))
      (node (ref "R05M") (pin "2") (pinfunction "2_2") (pintype "passive"))
      (node (ref "R06B") (pin "1") (pinfunction "1_1") (pintype "passive"))
      (node (ref "R06D") (pin "1") (pinfunction "1_1") (pintype "passive"))
      (node (ref "R06M") (pin "2") (pinfunction "2_2") (pintype "passive"))
      (node (ref "R07B") (pin "1") (pinfunction "1_1") (pintype "passive"))
      (node (ref "R07D") (pin "2") (pinfunction "2_2") (pintype "passive"))
      (node (ref "R08B") (pin "1") (pinfunction "1_1") (pintype "passive"))
      (node (ref "R09B") (pin "1") (pinfunction "1_1") (pintype "passive"))
      (node (ref "R10B") (pin "1") (pinfunction "1_1") (pintype "passive"))
      (node (ref "R14B") (pin "1") (pinfunction "1_1") (pintype "passive"))
      (node (ref "R16B") (pin "1") (pinfunction "1_1") (pintype "passive"))
      (node (ref "R18B") (pin "1") (pinfunction "A_1") (pintype "passive"))
      (node (ref "R21B") (pin "1") (pinfunction "1_1") (pintype "passive"))
      (node (ref "SJ1") (pin "1") (pinfunction "1_1") (pintype "passive"))
      (node (ref "U01B") (pin "8") (pinfunction "VSS_8") (pintype "bidirectional"))
      (node (ref "U01M") (pin "17") (pinfunction "GND_17") (pintype "power_in"))
      (node (ref "U01S") (pin "12") (pinfunction "SDO_12") (pintype "bidirectional"))
      (node (ref "U01S") (pin "2") (pinfunction "GND_2") (pintype "bidirectional"))
      (node (ref "U01S") (pin "4") (pinfunction "GND_4") (pintype "bidirectional"))
      (node (ref "U01S") (pin "5") (pinfunction "GND_5") (pintype "bidirectional"))
      (node (ref "U02B") (pin "2") (pinfunction "GND_2") (pintype "bidirectional"))
      (node (ref "U02M") (pin "17") (pinfunction "GND_17") (pintype "power_in"))
      (node (ref "U03B") (pin "3") (pinfunction "GND_3") (pintype "bidirectional"))
      (node (ref "U03B") (pin "7") (pinfunction "PGND_7") (pintype "bidirectional"))
      (node (ref "U03B") (pin "9") (pinfunction "PGND_9") (pintype "bidirectional"))
      (node (ref "U03M") (pin "#2") (pinfunction "GND_#2") (pintype "power_in"))
      (node (ref "U03M") (pin "#21") (pinfunction "GND_#21") (pintype "power_in"))
      (node (ref "U03M") (pin "2") (pinfunction "GND_2") (pintype "power_in"))
      (node (ref "U03M") (pin "21") (pinfunction "GND_21") (pintype "power_in"))
      (node (ref "U03M") (pin "@2") (pinfunction "GND_@2") (pintype "power_in"))
      (node (ref "U03M") (pin "@21") (pinfunction "GND_@21") (pintype "power_in"))
      (node (ref "U04B") (pin "5") (pinfunction "GND_5") (pintype "bidirectional"))
      (node (ref "U05B") (pin "2") (pinfunction "GND_2") (pintype "bidirectional"))
      (node (ref "U05B") (pin "3") (pinfunction "GND_3") (pintype "bidirectional"))
      (node (ref "U05B") (pin "6") (pinfunction "GND_6") (pintype "bidirectional"))
      (node (ref "U05B") (pin "7") (pinfunction "GND_7") (pintype "bidirectional"))
      (node (ref "U1") (pin "2") (pinfunction "VSS_2") (pintype "power_in"))
    )
    (net (code "27") (name "JTAG_TCK") (class "Default")
      (node (ref "J02M") (pin "3") (pinfunction "3_3") (pintype "bidirectional"))
      (node (ref "U03M") (pin "#19") (pinfunction "D6_#19") (pintype "bidirectional"))
      (node (ref "U03M") (pin "19") (pinfunction "D6_19") (pintype "bidirectional"))
      (node (ref "U03M") (pin "@19") (pinfunction "D6_@19") (pintype "bidirectional"))
    )
    (net (code "28") (name "JTAG_TMS") (class "Default")
      (node (ref "J02M") (pin "1") (pinfunction "1_1") (pintype "bidirectional"))
      (node (ref "U03M") (pin "#20") (pinfunction "D7_#20") (pintype "bidirectional"))
      (node (ref "U03M") (pin "20") (pinfunction "D7_20") (pintype "bidirectional"))
      (node (ref "U03M") (pin "@20") (pinfunction "D7_@20") (pintype "bidirectional"))
    )
    (net (code "29") (name "JTAG_TRST") (class "Default")
      (node (ref "J02M") (pin "5") (pinfunction "5_5") (pintype "bidirectional"))
      (node (ref "R02S") (pin "1") (pinfunction "1_1") (pintype "passive"))
      (node (ref "U03M") (pin "#16") (pinfunction "D3_#16") (pintype "bidirectional"))
      (node (ref "U03M") (pin "16") (pinfunction "D3_16") (pintype "bidirectional"))
      (node (ref "U03M") (pin "@16") (pinfunction "D3_@16") (pintype "bidirectional"))
    )
    (net (code "30") (name "LE") (class "Default")
      (node (ref "J02S") (pin "6") (pinfunction "LE_6") (pintype "bidirectional"))
      (node (ref "U02M") (pin "10") (pinfunction "GP1_10") (pintype "bidirectional"))
    )
    (net (code "31") (name "MCU_RST") (class "Default")
      (node (ref "J02M") (pin "4") (pinfunction "4_4") (pintype "bidirectional"))
      (node (ref "U03M") (pin "#23") (pinfunction "~{RST}_#23") (pintype "bidirectional"))
      (node (ref "U03M") (pin "23") (pinfunction "~{RST}_23") (pintype "bidirectional"))
      (node (ref "U03M") (pin "@23") (pinfunction "~{RST}_@23") (pintype "bidirectional"))
    )
    (net (code "32") (name "MCU_RX") (class "Default")
      (node (ref "J01M") (pin "4") (pinfunction "4_4") (pintype "passive"))
      (node (ref "U03M") (pin "#4") (pinfunction "RX_#4") (pintype "bidirectional"))
      (node (ref "U03M") (pin "4") (pinfunction "RX_4") (pintype "bidirectional"))
      (node (ref "U03M") (pin "@4") (pinfunction "RX_@4") (pintype "bidirectional"))
    )
    (net (code "33") (name "MCU_TX") (class "Default")
      (node (ref "J01M") (pin "5") (pinfunction "5_5") (pintype "passive"))
      (node (ref "U03M") (pin "#3") (pinfunction "TX_#3") (pintype "bidirectional"))
      (node (ref "U03M") (pin "3") (pinfunction "TX_3") (pintype "bidirectional"))
      (node (ref "U03M") (pin "@3") (pinfunction "TX_@3") (pintype "bidirectional"))
    )
    (net (code "34") (name "MCU_USB_DM") (class "Default")
      (node (ref "J07B") (pin "D-") (pinfunction "D-_D-") (pintype "bidirectional"))
    )
    (net (code "35") (name "MCU_USB_DP") (class "Default")
      (node (ref "J07B") (pin "D+") (pinfunction "D+_D+") (pintype "bidirectional"))
    )
    (net (code "36") (name "MCU_VBAT") (class "Default")
      (node (ref "J03M") (pin "1") (pinfunction "+_1") (pintype "power_in"))
      (node (ref "U03M") (pin "#22") (pinfunction "VBAT_#22") (pintype "power_in"))
      (node (ref "U03M") (pin "22") (pinfunction "VBAT_22") (pintype "power_in"))
      (node (ref "U03M") (pin "@22") (pinfunction "VBAT_@22") (pintype "power_in"))
    )
    (net (code "37") (name "MCU_VIN") (class "Default")
      (node (ref "U03M") (pin "#1") (pinfunction "VIN_#1") (pintype "power_in"))
      (node (ref "U03M") (pin "1") (pinfunction "VIN_1") (pintype "power_in"))
      (node (ref "U03M") (pin "@1") (pinfunction "VIN_@1") (pintype "power_in"))
    )
    (net (code "38") (name "MCU_WKP") (class "Default")
      (node (ref "SW01M") (pin "3") (pinfunction "2_3") (pintype "passive"))
      (node (ref "U03M") (pin "#5") (pinfunction "WKP_#5") (pintype "bidirectional"))
      (node (ref "U03M") (pin "5") (pinfunction "WKP_5") (pintype "bidirectional"))
      (node (ref "U03M") (pin "@5") (pinfunction "WKP_@5") (pintype "bidirectional"))
    )
    (net (code "39") (name "N$31") (class "Default")
      (node (ref "U02M") (pin "14") (pinfunction "GP5_14") (pintype "bidirectional"))
    )
    (net (code "40") (name "NEG_EN") (class "Default")
      (node (ref "U02M") (pin "13") (pinfunction "GP4_13") (pintype "bidirectional"))
      (node (ref "U03B") (pin "2") (pinfunction "~{SHDN1}_2") (pintype "bidirectional"))
    )
    (net (code "41") (name "NFB1") (class "Default")
      (node (ref "C08B") (pin "1") (pinfunction "1_1") (pintype "passive"))
      (node (ref "R13B") (pin "1") (pinfunction "1_1") (pintype "passive"))
      (node (ref "R14B") (pin "2") (pinfunction "2_2") (pintype "passive"))
      (node (ref "U03B") (pin "1") (pinfunction "NFB1_1") (pintype "bidirectional"))
    )
    (net (code "42") (name "Net-(C02B-Pad2)") (class "Default")
      (node (ref "C02B") (pin "2") (pinfunction "2_2") (pintype "passive"))
      (node (ref "J04B") (pin "2") (pinfunction "2_2") (pintype "passive"))
      (node (ref "J05B") (pin "1") (pinfunction "1_1") (pintype "passive"))
      (node (ref "U01B") (pin "2") (pinfunction "BAT_2") (pintype "bidirectional"))
      (node (ref "U01B") (pin "3") (pinfunction "BAT_3") (pintype "bidirectional"))
    )
    (net (code "43") (name "Net-(C07B-Pad2)") (class "Default")
      (node (ref "C07B") (pin "2") (pinfunction "2_2") (pintype "passive"))
      (node (ref "D03B") (pin "A") (pinfunction "A_A") (pintype "passive"))
      (node (ref "D04B") (pin "C") (pinfunction "C_C") (pintype "passive"))
    )
    (net (code "44") (name "Net-(D01B-PadA)") (class "Default")
      (node (ref "D01B") (pin "A") (pinfunction "A_A") (pintype "passive"))
      (node (ref "R01B") (pin "2") (pinfunction "2_2") (pintype "passive"))
    )
    (net (code "45") (name "Net-(D01S-PadA)") (class "Default")
      (node (ref "D01S") (pin "A") (pinfunction "A_A") (pintype "passive"))
      (node (ref "R01S") (pin "1") (pinfunction "1_1") (pintype "passive"))
    )
    (net (code "46") (name "Net-(D02B-PadA)") (class "Default")
      (node (ref "D02B") (pin "A") (pinfunction "A_A") (pintype "passive"))
      (node (ref "R02B") (pin "1") (pinfunction "1_1") (pintype "passive"))
    )
    (net (code "47") (name "Net-(D06B-PadA)") (class "Default")
      (node (ref "D06B") (pin "A") (pinfunction "A_A") (pintype "passive"))
      (node (ref "R20B") (pin "2") (pinfunction "2_2") (pintype "passive"))
    )
    (net (code "48") (name "Net-(J02S-CE1)") (class "Default")
      (node (ref "J02S") (pin "9") (pinfunction "CE1_9") (pintype "bidirectional"))
      (node (ref "R02D") (pin "1") (pinfunction "1_1") (pintype "passive"))
    )
    (net (code "49") (name "Net-(J02S-GMODE1)") (class "Default")
      (node (ref "J02S") (pin "28") (pinfunction "GMODE1_28") (pintype "bidirectional"))
      (node (ref "R04D") (pin "2") (pinfunction "2_2") (pintype "passive"))
    )
    (net (code "50") (name "Net-(J02S-RL)") (class "Default")
      (node (ref "J02S") (pin "29") (pinfunction "RL_29") (pintype "bidirectional"))
      (node (ref "SJ1") (pin "2") (pinfunction "2_2") (pintype "passive"))
    )
    (net (code "51") (name "Net-(J02S-U1CE1)") (class "Default")
      (node (ref "J02S") (pin "31") (pinfunction "U1CE1_31") (pintype "bidirectional"))
      (node (ref "R06D") (pin "2") (pinfunction "2_2") (pintype "passive"))
    )
    (net (code "52") (name "Net-(J02S-U1CE2)") (class "Default")
      (node (ref "J02S") (pin "30") (pinfunction "U1CE2_30") (pintype "bidirectional"))
      (node (ref "R05D") (pin "2") (pinfunction "2_2") (pintype "passive"))
    )
    (net (code "53") (name "Net-(J02S-U2CE1)") (class "Default")
      (node (ref "J02S") (pin "36") (pinfunction "U2CE1_36") (pintype "bidirectional"))
      (node (ref "R09D") (pin "2") (pinfunction "2_2") (pintype "passive"))
    )
    (net (code "54") (name "Net-(J02S-U2CE2)") (class "Default")
      (node (ref "J02S") (pin "35") (pinfunction "U2CE2_35") (pintype "bidirectional"))
      (node (ref "R08D") (pin "2") (pinfunction "2_2") (pintype "passive"))
    )
    (net (code "55") (name "Net-(J02S-U2CKV)") (class "Default")
      (node (ref "J02S") (pin "38") (pinfunction "U2CKV_38") (pintype "bidirectional"))
      (node (ref "R10D") (pin "1") (pinfunction "1_1") (pintype "passive"))
    )
    (net (code "56") (name "Net-(J02S-U2SPV)") (class "Default")
      (node (ref "J02S") (pin "37") (pinfunction "U2SPV_37") (pintype "bidirectional"))
      (node (ref "R11D") (pin "1") (pinfunction "1_1") (pintype "passive"))
    )
    (net (code "57") (name "Net-(J02S-VBORDER)") (class "Default")
      (node (ref "J02S") (pin "34") (pinfunction "VBORDER_34") (pintype "bidirectional"))
      (node (ref "R07D") (pin "1") (pinfunction "1_1") (pintype "passive"))
    )
    (net (code "58") (name "Net-(R18B-E)") (class "Default")
      (node (ref "R17B") (pin "1") (pinfunction "1_1") (pintype "passive"))
      (node (ref "R18B") (pin "3") (pinfunction "E_3") (pintype "passive"))
    )
    (net (code "59") (name "Net-(R18B-S)") (class "Default")
      (node (ref "R18B") (pin "2") (pinfunction "S_2") (pintype "passive"))
      (node (ref "U06B") (pin "5") (pinfunction "+IN2_5") (pintype "input"))
    )
    (net (code "60") (name "Net-(TP01B-TP)") (class "Default")
      (node (ref "R11B") (pin "1") (pinfunction "1_1") (pintype "passive"))
      (node (ref "TP01B") (pin "P$1") (pinfunction "TP_P$1") (pintype "bidirectional"))
      (node (ref "U02B") (pin "1") (pinfunction "EN_1") (pintype "bidirectional"))
    )
    (net (code "61") (name "Net-(U$1-TP)") (class "Default")
      (node (ref "U$1") (pin "P$1") (pinfunction "TP_P$1") (pintype "bidirectional"))
      (node (ref "U01M") (pin "4") (pinfunction "/RST_4") (pintype "input"))
    )
    (net (code "62") (name "Net-(U$2-TP)") (class "Default")
      (node (ref "U$2") (pin "P$1") (pinfunction "TP_P$1") (pintype "bidirectional"))
      (node (ref "U01M") (pin "7") (pinfunction "INT_7") (pintype "output"))
    )
    (net (code "63") (name "Net-(U$3-TP)") (class "Default")
      (node (ref "U$3") (pin "P$1") (pinfunction "TP_P$1") (pintype "bidirectional"))
      (node (ref "U02M") (pin "4") (pinfunction "/RST_4") (pintype "input"))
    )
    (net (code "64") (name "Net-(U$4-TP)") (class "Default")
      (node (ref "U$4") (pin "P$1") (pinfunction "TP_P$1") (pintype "bidirectional"))
      (node (ref "U02M") (pin "7") (pinfunction "INT_7") (pintype "output"))
    )
    (net (code "65") (name "Net-(U1-PROG)") (class "Default")
      (node (ref "R21B") (pin "2") (pinfunction "2_2") (pintype "passive"))
      (node (ref "U1") (pin "5") (pinfunction "PROG_5") (pintype "input"))
    )
    (net (code "66") (name "Net-(U1-STAT)") (class "Default")
      (node (ref "D06B") (pin "C") (pinfunction "C_C") (pintype "passive"))
      (node (ref "U1") (pin "1") (pinfunction "STAT_1") (pintype "output"))
    )
    (net (code "67") (name "Net-(U01B-EN1)") (class "Default")
      (node (ref "R03B") (pin "1") (pinfunction "1_1") (pintype "passive"))
      (node (ref "U01B") (pin "6") (pinfunction "EN1_6") (pintype "bidirectional"))
    )
    (net (code "68") (name "Net-(U01B-EN2)") (class "Default")
      (node (ref "R04B") (pin "1") (pinfunction "1_1") (pintype "passive"))
      (node (ref "U01B") (pin "5") (pinfunction "EN2_5") (pintype "bidirectional"))
    )
    (net (code "69") (name "Net-(U01B-ILIM)") (class "Default")
      (node (ref "R08B") (pin "2") (pinfunction "2_2") (pintype "passive"))
      (node (ref "U01B") (pin "12") (pinfunction "ILIM_12") (pintype "bidirectional"))
    )
    (net (code "70") (name "Net-(U01B-ISET)") (class "Default")
      (node (ref "R09B") (pin "2") (pinfunction "2_2") (pintype "passive"))
      (node (ref "U01B") (pin "16") (pinfunction "ISET_16") (pintype "bidirectional"))
    )
    (net (code "71") (name "Net-(U01B-TMR)") (class "Default")
      (node (ref "R06B") (pin "2") (pinfunction "2_2") (pintype "passive"))
      (node (ref "U01B") (pin "14") (pinfunction "TMR_14") (pintype "bidirectional"))
    )
    (net (code "72") (name "Net-(U01B-TS)") (class "Default")
      (node (ref "R10B") (pin "2") (pinfunction "2_2") (pintype "passive"))
      (node (ref "U01B") (pin "1") (pinfunction "TS_1") (pintype "bidirectional"))
    )
    (net (code "73") (name "Net-(U01M-A0)") (class "Default")
      (node (ref "R01M") (pin "1") (pinfunction "1_1") (pintype "passive"))
      (node (ref "U01M") (pin "3") (pinfunction "A0_3") (pintype "input"))
    )
    (net (code "74") (name "Net-(U01M-A1)") (class "Default")
      (node (ref "R02M") (pin "1") (pinfunction "1_1") (pintype "passive"))
      (node (ref "U01M") (pin "2") (pinfunction "A1_2") (pintype "input"))
    )
    (net (code "75") (name "Net-(U01M-A2)") (class "Default")
      (node (ref "R03M") (pin "1") (pinfunction "1_1") (pintype "passive"))
      (node (ref "U01M") (pin "1") (pinfunction "A2_1") (pintype "input"))
    )
    (net (code "76") (name "Net-(U01S-CS)") (class "Default")
      (node (ref "C02S") (pin "1") (pinfunction "1_1") (pintype "passive"))
      (node (ref "C03S") (pin "1") (pinfunction "1_1") (pintype "passive"))
      (node (ref "C04S") (pin "1") (pinfunction "1_1") (pintype "passive"))
      (node (ref "U01S") (pin "1") (pinfunction "VDD_1") (pintype "bidirectional"))
      (node (ref "U01S") (pin "6") (pinfunction "VS_6") (pintype "bidirectional"))
      (node (ref "U01S") (pin "7") (pinfunction "CS_7") (pintype "bidirectional"))
    )
    (net (code "77") (name "Net-(U01S-INT1)") (class "Default")
      (node (ref "R02S") (pin "2") (pinfunction "2_2") (pintype "passive"))
      (node (ref "U01S") (pin "8") (pinfunction "INT1_8") (pintype "bidirectional"))
    )
    (net (code "78") (name "Net-(U02B-LX)") (class "Default")
      (node (ref "L01B") (pin "1") (pinfunction "1_1") (pintype "passive"))
      (node (ref "U02B") (pin "3") (pinfunction "LX_3") (pintype "bidirectional"))
    )
    (net (code "79") (name "Net-(U02M-A0)") (class "Default")
      (node (ref "R04M") (pin "1") (pinfunction "1_1") (pintype "passive"))
      (node (ref "U02M") (pin "3") (pinfunction "A0_3") (pintype "input"))
    )
    (net (code "80") (name "Net-(U02M-A1)") (class "Default")
      (node (ref "R05M") (pin "1") (pinfunction "1_1") (pintype "passive"))
      (node (ref "U02M") (pin "2") (pinfunction "A1_2") (pintype "input"))
    )
    (net (code "81") (name "Net-(U02M-A2)") (class "Default")
      (node (ref "R06M") (pin "1") (pinfunction "1_1") (pintype "passive"))
      (node (ref "U02M") (pin "1") (pinfunction "A2_1") (pintype "input"))
    )
    (net (code "82") (name "Net-(U03B-SW1)") (class "Default")
      (node (ref "C07B") (pin "1") (pinfunction "1_1") (pintype "passive"))
      (node (ref "L02B") (pin "P$2") (pinfunction "P$2_P$2") (pintype "bidirectional"))
      (node (ref "U03B") (pin "10") (pinfunction "SW1_10") (pintype "bidirectional"))
    )
    (net (code "83") (name "Net-(U03B-SW2)") (class "Default")
      (node (ref "D05B") (pin "A") (pinfunction "A_A") (pintype "passive"))
      (node (ref "L03B") (pin "P$2") (pinfunction "P$2_P$2") (pintype "bidirectional"))
      (node (ref "U03B") (pin "6") (pinfunction "SW2_6") (pintype "bidirectional"))
    )
    (net (code "84") (name "OE") (class "Default")
      (node (ref "J02S") (pin "7") (pinfunction "OE_7") (pintype "bidirectional"))
      (node (ref "U02M") (pin "11") (pinfunction "GP2_11") (pintype "bidirectional"))
    )
    (net (code "85") (name "POS_EN") (class "Default")
      (node (ref "U02M") (pin "16") (pinfunction "GP7_16") (pintype "bidirectional"))
      (node (ref "U03B") (pin "4") (pinfunction "~{SHDN2}_4") (pintype "bidirectional"))
    )
    (net (code "86") (name "SCL") (class "Default")
      (node (ref "R08M") (pin "2") (pinfunction "2_2") (pintype "passive"))
      (node (ref "U01M") (pin "19") (pinfunction "SCL_19") (pintype "bidirectional"))
      (node (ref "U01S") (pin "14") (pinfunction "SCL_14") (pintype "bidirectional"))
      (node (ref "U02M") (pin "19") (pinfunction "SCL_19") (pintype "bidirectional"))
      (node (ref "U03M") (pin "#14") (pinfunction "D1_#14") (pintype "bidirectional"))
      (node (ref "U03M") (pin "14") (pinfunction "D1_14") (pintype "bidirectional"))
      (node (ref "U03M") (pin "@14") (pinfunction "D1_@14") (pintype "bidirectional"))
    )
    (net (code "87") (name "SDA") (class "Default")
      (node (ref "R09M") (pin "2") (pinfunction "2_2") (pintype "passive"))
      (node (ref "U01M") (pin "20") (pinfunction "SDA_20") (pintype "bidirectional"))
      (node (ref "U01S") (pin "13") (pinfunction "SDA_13") (pintype "bidirectional"))
      (node (ref "U02M") (pin "20") (pinfunction "SDA_20") (pintype "bidirectional"))
      (node (ref "U03M") (pin "#13") (pinfunction "D0_#13") (pintype "bidirectional"))
      (node (ref "U03M") (pin "13") (pinfunction "D0_13") (pintype "bidirectional"))
      (node (ref "U03M") (pin "@13") (pinfunction "D0_@13") (pintype "bidirectional"))
    )
    (net (code "88") (name "SD_CD") (class "Default")
      (node (ref "J01S") (pin "CD1") (pinfunction "CARD_DETECT_CD1") (pintype "passive"))
      (node (ref "U$5") (pin "P$1") (pinfunction "TP_P$1") (pintype "bidirectional"))
    )
    (net (code "89") (name "SHR") (class "Default")
      (node (ref "J02S") (pin "8") (pinfunction "SHR_8") (pintype "bidirectional"))
      (node (ref "R01D") (pin "2") (pinfunction "2_2") (pintype "passive"))
      (node (ref "R03D") (pin "1") (pinfunction "1_1") (pintype "passive"))
    )
    (net (code "90") (name "SMPS_CTRL") (class "Default")
      (node (ref "Q01B") (pin "1") (pinfunction "G_1") (pintype "passive"))
      (node (ref "R12B") (pin "1") (pinfunction "1_1") (pintype "passive"))
      (node (ref "U02M") (pin "15") (pinfunction "GP6_15") (pintype "bidirectional"))
    )
    (net (code "91") (name "SPH") (class "Default")
      (node (ref "J02S") (pin "11") (pinfunction "SPH_11") (pintype "bidirectional"))
      (node (ref "U02M") (pin "12") (pinfunction "GP3_12") (pintype "bidirectional"))
    )
    (net (code "92") (name "SPI_CS") (class "Default")
      (node (ref "D01S") (pin "C") (pinfunction "C_C") (pintype "passive"))
      (node (ref "J01S") (pin "2") (pinfunction "CS_2") (pintype "input"))
      (node (ref "U03M") (pin "#10") (pinfunction "A2_#10") (pintype "bidirectional"))
      (node (ref "U03M") (pin "10") (pinfunction "A2_10") (pintype "bidirectional"))
      (node (ref "U03M") (pin "@10") (pinfunction "A2_@10") (pintype "bidirectional"))
    )
    (net (code "93") (name "SPI_MISO") (class "Default")
      (node (ref "J01S") (pin "7") (pinfunction "DATA_OUT_7") (pintype "output"))
      (node (ref "U03M") (pin "#8") (pinfunction "A4_#8") (pintype "bidirectional"))
      (node (ref "U03M") (pin "8") (pinfunction "A4_8") (pintype "bidirectional"))
      (node (ref "U03M") (pin "@8") (pinfunction "A4_@8") (pintype "bidirectional"))
    )
    (net (code "94") (name "SPI_MOSI") (class "Default")
      (node (ref "J01S") (pin "3") (pinfunction "DATA_IN_3") (pintype "input"))
      (node (ref "U03M") (pin "#7") (pinfunction "A5_#7") (pintype "bidirectional"))
      (node (ref "U03M") (pin "7") (pinfunction "A5_7") (pintype "bidirectional"))
      (node (ref "U03M") (pin "@7") (pinfunction "A5_@7") (pintype "bidirectional"))
    )
    (net (code "95") (name "SPI_SCK") (class "Default")
      (node (ref "J01S") (pin "5") (pinfunction "SCLK_5") (pintype "input"))
      (node (ref "R01S") (pin "2") (pinfunction "2_2") (pintype "passive"))
      (node (ref "U03M") (pin "#9") (pinfunction "A3_#9") (pintype "bidirectional"))
      (node (ref "U03M") (pin "9") (pinfunction "A3_9") (pintype "bidirectional"))
      (node (ref "U03M") (pin "@9") (pinfunction "A3_@9") (pintype "bidirectional"))
    )
    (net (code "96") (name "U1CKV") (class "Default")
      (node (ref "J02S") (pin "33") (pinfunction "U1CKV_33") (pintype "bidirectional"))
      (node (ref "R10D") (pin "2") (pinfunction "2_2") (pintype "passive"))
      (node (ref "U03M") (pin "#18") (pinfunction "D5_#18") (pintype "bidirectional"))
      (node (ref "U03M") (pin "18") (pinfunction "D5_18") (pintype "bidirectional"))
      (node (ref "U03M") (pin "@18") (pinfunction "D5_@18") (pintype "bidirectional"))
    )
    (net (code "97") (name "U1SPV") (class "Default")
      (node (ref "J02S") (pin "32") (pinfunction "U1SPV_32") (pintype "bidirectional"))
      (node (ref "R11D") (pin "2") (pinfunction "2_2") (pintype "passive"))
      (node (ref "U03M") (pin "#17") (pinfunction "D4_#17") (pintype "bidirectional"))
      (node (ref "U03M") (pin "17") (pinfunction "D4_17") (pintype "bidirectional"))
      (node (ref "U03M") (pin "@17") (pinfunction "D4_@17") (pintype "bidirectional"))
    )
    (net (code "98") (name "VBUS") (class "Default")
      (node (ref "C01B") (pin "2") (pinfunction "2_2") (pintype "passive"))
      (node (ref "C19B") (pin "2") (pinfunction "2_2") (pintype "passive"))
      (node (ref "J01B") (pin "1") (pinfunction "1_1") (pintype "passive"))
      (node (ref "J07B") (pin "VBUS") (pinfunction "VBUS_VBUS") (pintype "bidirectional"))
      (node (ref "R20B") (pin "1") (pinfunction "1_1") (pintype "passive"))
      (node (ref "U01B") (pin "13") (pinfunction "IN_13") (pintype "bidirectional"))
      (node (ref "U1") (pin "4") (pinfunction "VIN_4") (pintype "power_in"))
    )
    (net (code "99") (name "VCOM") (class "Default")
      (node (ref "C17B") (pin "2") (pinfunction "2_2") (pintype "passive"))
      (node (ref "J02S") (pin "22") (pinfunction "VCOM_22") (pintype "bidirectional"))
      (node (ref "J13B") (pin "1") (pinfunction "1_1") (pintype "passive"))
      (node (ref "U06B") (pin "6") (pinfunction "-IN2_6") (pintype "input"))
      (node (ref "U06B") (pin "7") (pinfunction "OUT2_7") (pintype "output"))
    )
    (net (code "100") (name "VIN") (class "Default")
      (node (ref "C09B") (pin "2") (pinfunction "2_2") (pintype "passive"))
      (node (ref "J08B") (pin "1") (pinfunction "1_1") (pintype "passive"))
      (node (ref "L02B") (pin "P$1") (pinfunction "P$1_P$1") (pintype "bidirectional"))
      (node (ref "L03B") (pin "P$1") (pinfunction "P$1_P$1") (pintype "bidirectional"))
      (node (ref "Q01B") (pin "3") (pinfunction "D_3") (pintype "passive"))
      (node (ref "U03B") (pin "8") (pinfunction "VIN_8") (pintype "bidirectional"))
    )
    (net (code "101") (name "unconnected-(J01M-Pad2)") (class "Default")
      (node (ref "J01M") (pin "2") (pinfunction "2_2") (pintype "passive"))
    )
    (net (code "102") (name "unconnected-(J01S-CARD_DETECT1-PadCD2)") (class "Default")
      (node (ref "J01S") (pin "CD2") (pinfunction "CARD_DETECT1_CD2") (pintype "passive"))
    )
    (net (code "103") (name "unconnected-(J01S-DAT1-Pad8)") (class "Default")
      (node (ref "J01S") (pin "8") (pinfunction "DAT1_8") (pintype "bidirectional"))
    )
    (net (code "104") (name "unconnected-(J01S-DAT2-Pad1)") (class "Default")
      (node (ref "J01S") (pin "1") (pinfunction "DAT2_1") (pintype "bidirectional"))
    )
    (net (code "105") (name "unconnected-(J02S-NC-20-Pad20)") (class "Default")
      (node (ref "J02S") (pin "20") (pinfunction "NC-20_20") (pintype "bidirectional"))
    )
    (net (code "106") (name "unconnected-(J02S-NC-21-Pad21)") (class "Default")
      (node (ref "J02S") (pin "21") (pinfunction "NC-21_21") (pintype "bidirectional"))
    )
    (net (code "107") (name "unconnected-(J02S-NC-25-Pad25)") (class "Default")
      (node (ref "J02S") (pin "25") (pinfunction "NC-25_25") (pintype "bidirectional"))
    )
    (net (code "108") (name "unconnected-(J02S-NC-26-Pad26)") (class "Default")
      (node (ref "J02S") (pin "26") (pinfunction "NC-26_26") (pintype "bidirectional"))
    )
    (net (code "109") (name "unconnected-(J02S-NC-39-Pad39)") (class "Default")
      (node (ref "J02S") (pin "39") (pinfunction "NC-39_39") (pintype "bidirectional"))
    )
    (net (code "110") (name "unconnected-(J03B-PAD1-PadNC1)") (class "Default")
      (node (ref "J03B") (pin "NC1") (pinfunction "PAD1_NC1") (pintype "bidirectional"))
    )
    (net (code "111") (name "unconnected-(J03B-PAD2-PadNC2)") (class "Default")
      (node (ref "J03B") (pin "NC2") (pinfunction "PAD2_NC2") (pintype "bidirectional"))
    )
    (net (code "112") (name "unconnected-(U01S-INT2-Pad9)") (class "Default")
      (node (ref "U01S") (pin "9") (pinfunction "INT2_9") (pintype "bidirectional"))
    )
    (net (code "113") (name "unconnected-(U01S-NC-Pad3)") (class "Default")
      (node (ref "U01S") (pin "3") (pinfunction "NC_3") (pintype "bidirectional"))
    )
    (net (code "114") (name "unconnected-(U01S-NC-Pad10)") (class "Default")
      (node (ref "U01S") (pin "10") (pinfunction "NC_10") (pintype "bidirectional"))
    )
    (net (code "115") (name "unconnected-(U01S-NC-Pad11)") (class "Default")
      (node (ref "U01S") (pin "11") (pinfunction "NC_11") (pintype "bidirectional"))
    )
    (net (code "116") (name "unconnected-(U04B-NC-Pad4)") (class "Default")
      (node (ref "U04B") (pin "4") (pinfunction "NC_4") (pintype "bidirectional"))
    )
    (net (code "117") (name "unconnected-(U04B-NC-Pad8)") (class "Default")
      (node (ref "U04B") (pin "8") (pinfunction "NC_8") (pintype "bidirectional"))
    )
    (net (code "118") (name "unconnected-(U05B-NC-Pad4)") (class "Default")
      (node (ref "U05B") (pin "4") (pinfunction "NC_4") (pintype "bidirectional"))
    )
    (net (code "119") (name "unconnected-(U05B-NC-Pad5)") (class "Default")
      (node (ref "U05B") (pin "5") (pinfunction "NC_5") (pintype "bidirectional"))
    )
    (net (code "120") (name "unconnected-(U06B-+IN1-Pad3)") (class "Default")
      (node (ref "U06B") (pin "3") (pinfunction "+IN1_3") (pintype "input"))
    )
    (net (code "121") (name "unconnected-(U06B--IN1-Pad2)") (class "Default")
      (node (ref "U06B") (pin "2") (pinfunction "-IN1_2") (pintype "input"))
    )
    (net (code "122") (name "unconnected-(U06B-OUT1-Pad1)") (class "Default")
      (node (ref "U06B") (pin "1") (pinfunction "OUT1_1") (pintype "output"))
    )
  )
)
